# Seeeduino_LoRaWan.net
KiCad netlist of a schematic drawn in EAGLE
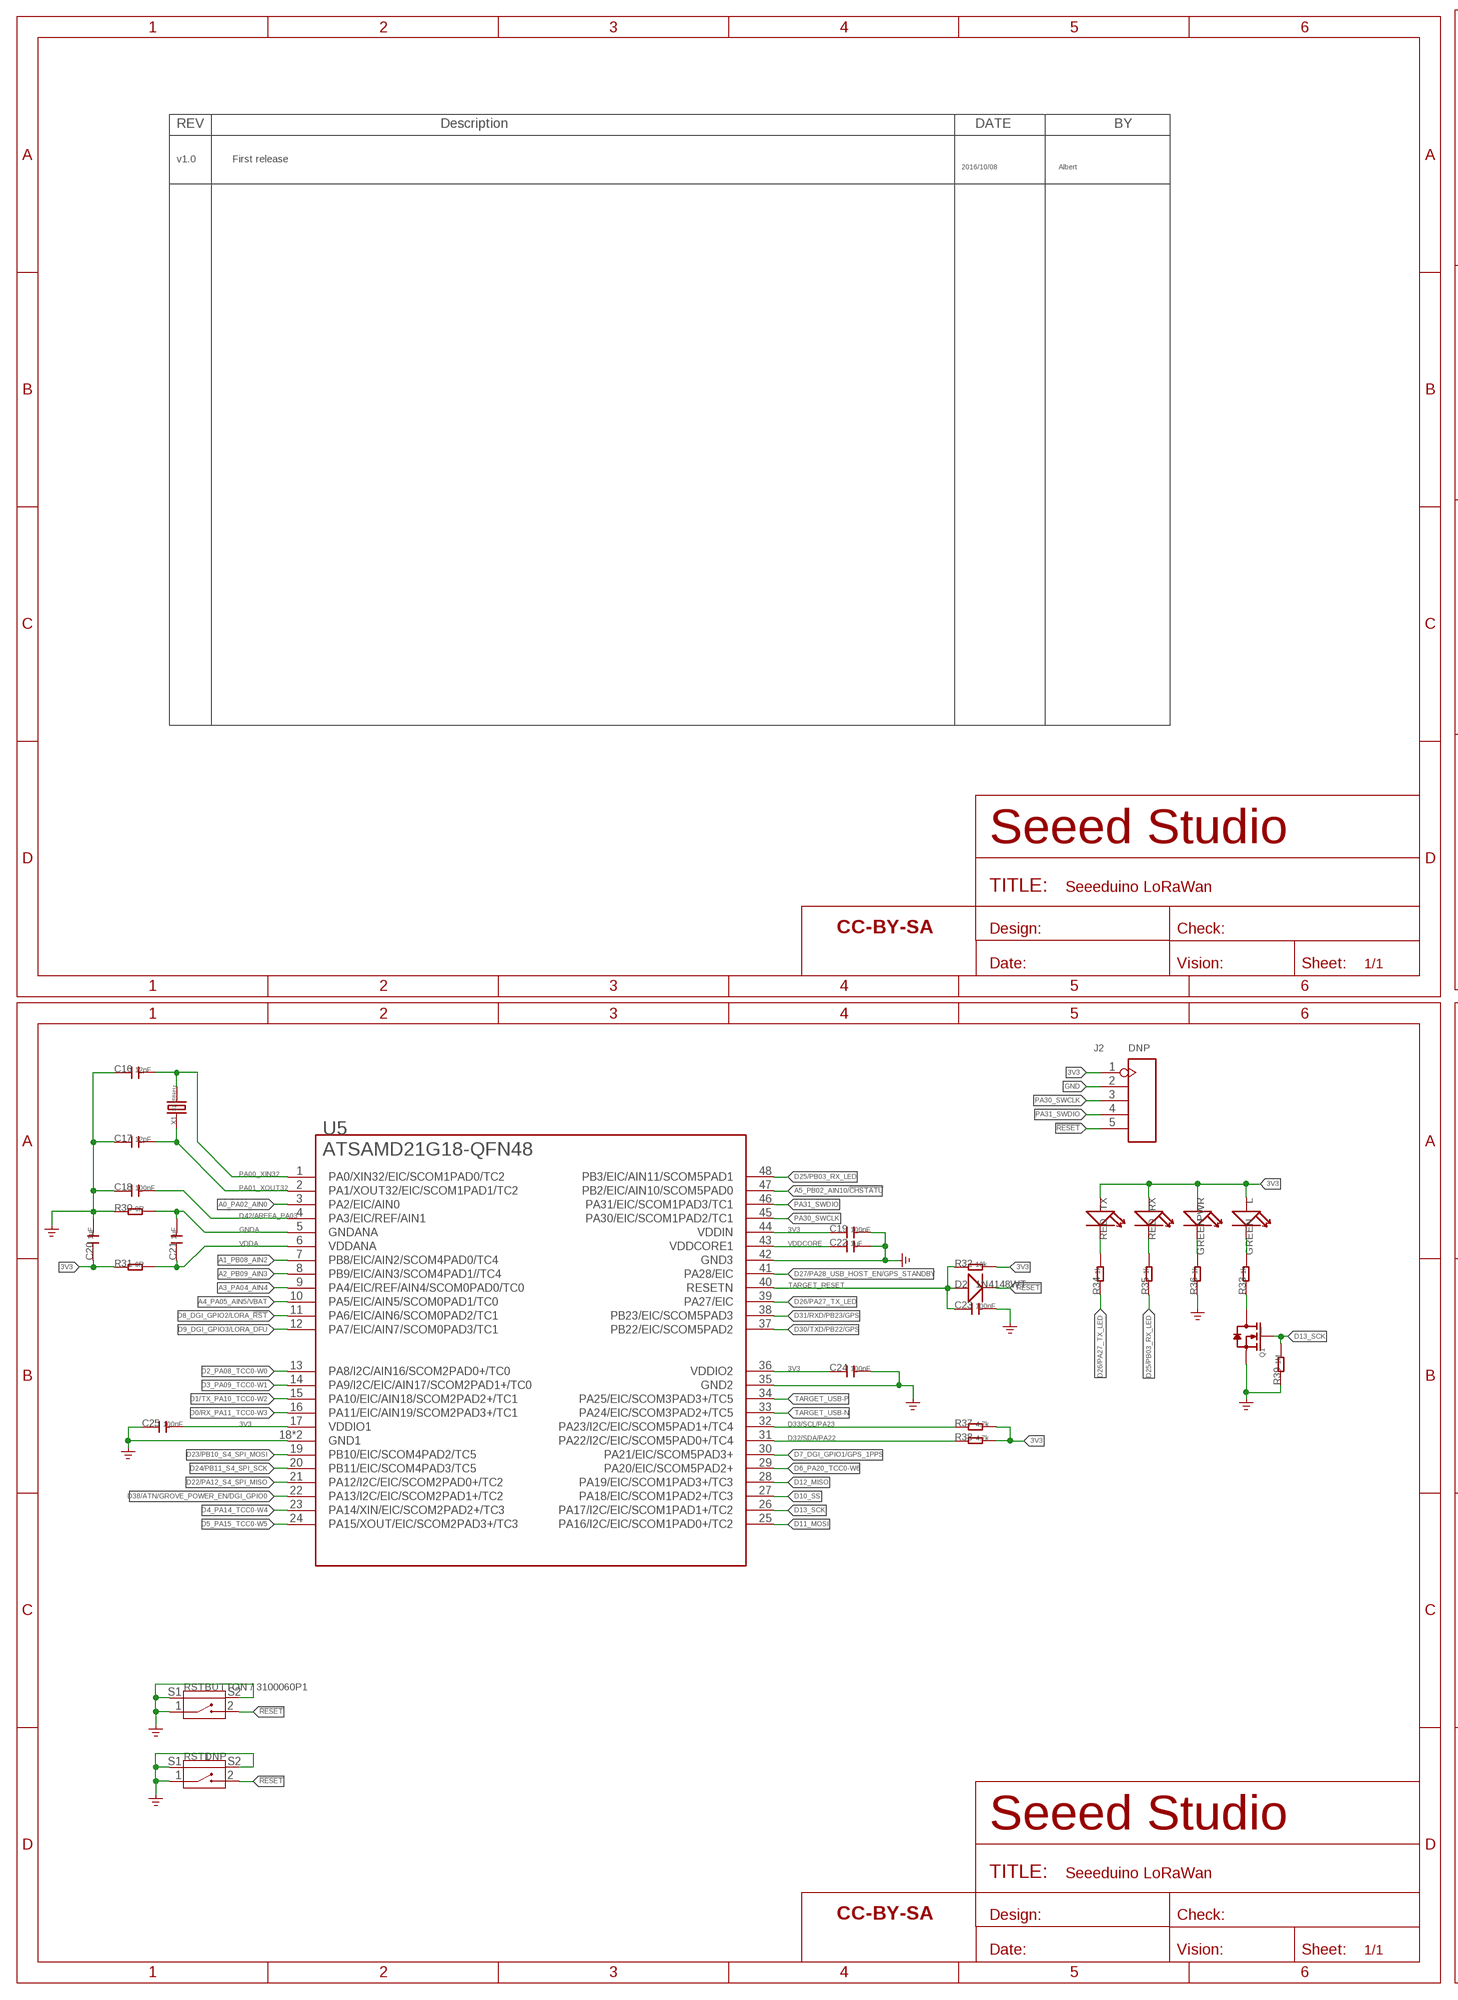
[diagram p0: schematic, sheet 1, part 1 of 2]
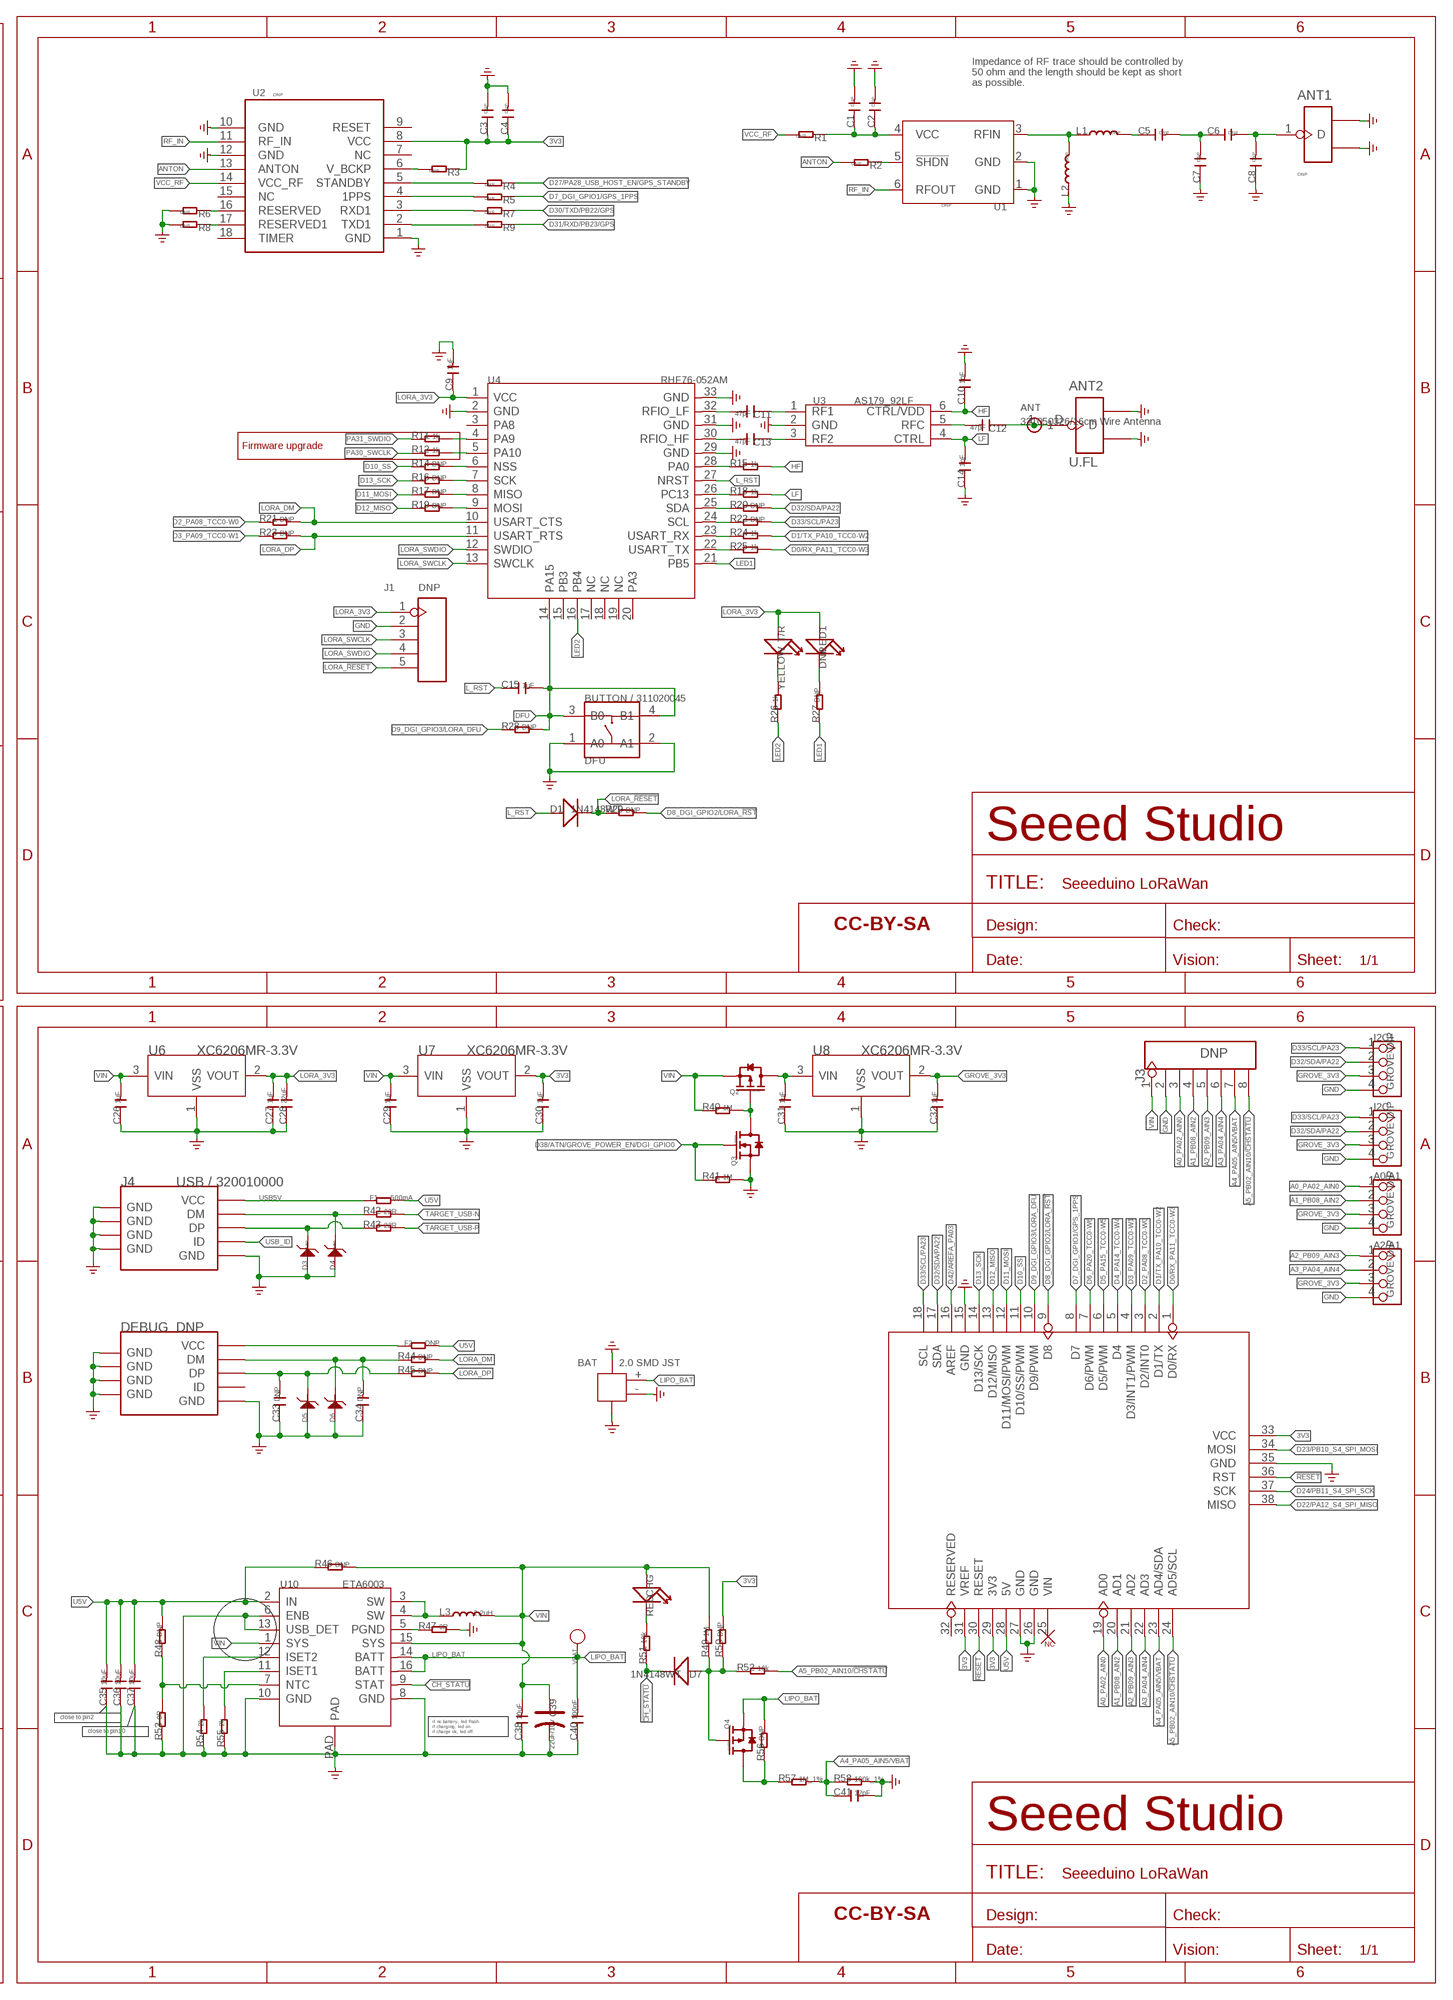
[diagram p1: schematic, sheet 1, part 2 of 2]

(export (version "E")
  (design (tool "Eeschema 10.0.6"))
  (components
    (comp (ref "A0/A1")
      (value "GROVE-DIP")
      (footprint "eagle-import:4P-2.0")
      (libsource (lib "eagle-import") (part "TWIG-4P-2.0-2.0"))
    )
    (comp (ref "A2/A1")
      (value "GROVE-DIP")
      (footprint "eagle-import:4P-2.0")
      (libsource (lib "eagle-import") (part "TWIG-4P-2.0-2.0"))
    )
    (comp (ref "ANT")
      (value "321050326/16cm Wire Antenna")
      (footprint "eagle-import:1P-65_35MIL")
      (libsource (lib "eagle-import") (part "HEADER-1P-35"))
    )
    (comp (ref "ANT1")
      (value "DNP")
      (footprint "eagle-import:ANT3-SMD-5.2X3.7X0.7MM")
      (fields (field (name "MPN") "ACD-5036-A3-CC-S"))
      (libsource (lib "eagle-import") (part "ANTENNA-ACD5036"))
    )
    (comp (ref "ANT2")
      (value "U.FL")
      (footprint "eagle-import:U-FL3P-SMD-2.6X2.6X1.0MM")
      (libsource (lib "eagle-import") (part "ANTENNA-U-FL"))
    )
    (comp (ref "BAT")
      (value "2.0 SMD JST")
      (footprint "eagle-import:HW2-SMD-2.0-90D")
      (libsource (lib "eagle-import") (part "JST-2P-SMD'2.0'"))
    )
    (comp (ref "C1")
      (value "DNP")
      (footprint "eagle-import:C0402")
      (libsource (lib "eagle-import") (part "C-0402"))
    )
    (comp (ref "C2")
      (value "DNP")
      (footprint "eagle-import:C0402")
      (libsource (lib "eagle-import") (part "C-0402"))
    )
    (comp (ref "C3")
      (value "DNP")
      (footprint "eagle-import:C0402")
      (libsource (lib "eagle-import") (part "C-0402"))
    )
    (comp (ref "C4")
      (value "DNP")
      (footprint "eagle-import:C0603")
      (libsource (lib "eagle-import") (part "C-0603"))
    )
    (comp (ref "C5")
      (value "DNP")
      (footprint "eagle-import:C0402")
      (libsource (lib "eagle-import") (part "C-0402"))
    )
    (comp (ref "C6")
      (value "DNP")
      (footprint "eagle-import:C0402")
      (libsource (lib "eagle-import") (part "C-0402"))
    )
    (comp (ref "C7")
      (value "DNP")
      (footprint "eagle-import:C0402")
      (libsource (lib "eagle-import") (part "C-0402"))
    )
    (comp (ref "C8")
      (value "DNP")
      (footprint "eagle-import:C0402")
      (libsource (lib "eagle-import") (part "C-0402"))
    )
    (comp (ref "C9")
      (value "1uF")
      (footprint "eagle-import:C0402")
      (libsource (lib "eagle-import") (part "C-0402"))
    )
    (comp (ref "C10")
      (value "1nF")
      (footprint "eagle-import:C0402")
      (libsource (lib "eagle-import") (part "C-0402"))
    )
    (comp (ref "C11")
      (value "47pF")
      (footprint "eagle-import:C0402")
      (libsource (lib "eagle-import") (part "C-0402"))
    )
    (comp (ref "C12")
      (value "47pF")
      (footprint "eagle-import:C0402")
      (libsource (lib "eagle-import") (part "C-0402"))
    )
    (comp (ref "C13")
      (value "47pF")
      (footprint "eagle-import:C0402")
      (libsource (lib "eagle-import") (part "C-0402"))
    )
    (comp (ref "C14")
      (value "1nF")
      (footprint "eagle-import:C0402")
      (libsource (lib "eagle-import") (part "C-0402"))
    )
    (comp (ref "C15")
      (value "1uF")
      (footprint "eagle-import:C0402")
      (libsource (lib "eagle-import") (part "C-0402"))
    )
    (comp (ref "C16")
      (value "12pF")
      (footprint "eagle-import:C0402")
      (libsource (lib "eagle-import") (part "C-0402"))
    )
    (comp (ref "C17")
      (value "12pF")
      (footprint "eagle-import:C0402")
      (libsource (lib "eagle-import") (part "C-0402"))
    )
    (comp (ref "C18")
      (value "100nF")
      (footprint "eagle-import:C0402")
      (libsource (lib "eagle-import") (part "C-0402"))
    )
    (comp (ref "C19")
      (value "100nF")
      (footprint "eagle-import:C0402")
      (libsource (lib "eagle-import") (part "C-0402"))
    )
    (comp (ref "C20")
      (value "1uF")
      (footprint "eagle-import:C0402")
      (libsource (lib "eagle-import") (part "C-0402"))
    )
    (comp (ref "C21")
      (value "1uF")
      (footprint "eagle-import:C0402")
      (libsource (lib "eagle-import") (part "C-0402"))
    )
    (comp (ref "C22")
      (value "1uF")
      (footprint "eagle-import:C0402")
      (libsource (lib "eagle-import") (part "C-0402"))
    )
    (comp (ref "C23")
      (value "100nF")
      (footprint "eagle-import:C0402")
      (libsource (lib "eagle-import") (part "C-0402"))
    )
    (comp (ref "C24")
      (value "100nF")
      (footprint "eagle-import:C0402")
      (libsource (lib "eagle-import") (part "C-0402"))
    )
    (comp (ref "C25")
      (value "100nF")
      (footprint "eagle-import:C0402")
      (libsource (lib "eagle-import") (part "C-0402"))
    )
    (comp (ref "C26")
      (value "1uF")
      (footprint "eagle-import:C0402")
      (libsource (lib "eagle-import") (part "C-0402"))
    )
    (comp (ref "C27")
      (value "1uF")
      (footprint "eagle-import:C0402")
      (libsource (lib "eagle-import") (part "C-0402"))
    )
    (comp (ref "C28")
      (value "22uF")
      (footprint "eagle-import:C0603")
      (libsource (lib "eagle-import") (part "C-0603"))
    )
    (comp (ref "C29")
      (value "1uF")
      (footprint "eagle-import:C0402")
      (libsource (lib "eagle-import") (part "C-0402"))
    )
    (comp (ref "C30")
      (value "1uF")
      (footprint "eagle-import:C0402")
      (libsource (lib "eagle-import") (part "C-0402"))
    )
    (comp (ref "C31")
      (value "1uF")
      (footprint "eagle-import:C0402")
      (libsource (lib "eagle-import") (part "C-0402"))
    )
    (comp (ref "C32")
      (value "1uF")
      (footprint "eagle-import:C0402")
      (libsource (lib "eagle-import") (part "C-0402"))
    )
    (comp (ref "C33")
      (value "DNP")
      (footprint "eagle-import:C0402")
      (libsource (lib "eagle-import") (part "C-0402"))
    )
    (comp (ref "C34")
      (value "DNP")
      (footprint "eagle-import:C0402")
      (libsource (lib "eagle-import") (part "C-0402"))
    )
    (comp (ref "C35")
      (value "10uF")
      (footprint "eagle-import:C0603")
      (libsource (lib "eagle-import") (part "C-0603"))
    )
    (comp (ref "C36")
      (value "10uF")
      (footprint "eagle-import:C0603")
      (libsource (lib "eagle-import") (part "C-0603"))
    )
    (comp (ref "C37")
      (value "10uF")
      (footprint "eagle-import:C0603")
      (libsource (lib "eagle-import") (part "C-0603"))
    )
    (comp (ref "C38")
      (value "10uF")
      (footprint "eagle-import:C0603")
      (libsource (lib "eagle-import") (part "C-0603"))
    )
    (comp (ref "C39")
      (value "22uF/10v")
      (footprint "eagle-import:AVX-A")
      (libsource (lib "eagle-import") (part "CAP-AVX-A"))
    )
    (comp (ref "C40")
      (value "100nF")
      (footprint "eagle-import:C0402")
      (libsource (lib "eagle-import") (part "C-0402"))
    )
    (comp (ref "C41")
      (value "12pF")
      (footprint "eagle-import:C0402")
      (libsource (lib "eagle-import") (part "C-0402"))
    )
    (comp (ref "CHG")
      (value "RED")
      (footprint "eagle-import:LED-0603")
      (libsource (lib "eagle-import") (part "LED'0603'"))
    )
    (comp (ref "D1")
      (value "1N4148WT")
      (footprint "eagle-import:SOD523")
      (libsource (lib "eagle-import") (part "D'0603'"))
    )
    (comp (ref "D2")
      (value "1N4148WT")
      (footprint "eagle-import:SOD523")
      (libsource (lib "eagle-import") (part "D'0603'"))
    )
    (comp (ref "D3")
      (value "DF2S6.8FS")
      (footprint "eagle-import:SOD-923")
      (libsource (lib "eagle-import") (part "D-ESD-2P'DF2S6.8FS'"))
    )
    (comp (ref "D4")
      (value "DF2S6.8FS")
      (footprint "eagle-import:SOD-923")
      (libsource (lib "eagle-import") (part "D-ESD-2P'DF2S6.8FS'"))
    )
    (comp (ref "D5")
      (value "DNP")
      (footprint "eagle-import:SOD-923")
      (libsource (lib "eagle-import") (part "D-ESD-2P'DF2S6.8FS'"))
    )
    (comp (ref "D6")
      (value "DNP")
      (footprint "eagle-import:SOD-923")
      (libsource (lib "eagle-import") (part "D-ESD-2P'DF2S6.8FS'"))
    )
    (comp (ref "D7")
      (value "1N4148WT")
      (footprint "eagle-import:SOD523")
      (libsource (lib "eagle-import") (part "D'0603'"))
    )
    (comp (ref "DEBUG")
      (value "DNP")
      (footprint "eagle-import:MICRO-USB")
      (libsource (lib "eagle-import") (part "USB-MINIUSB-5P-MICRO"))
    )
    (comp (ref "DFU")
      (value "BUTTON / 311020045")
      (footprint "eagle-import:SW4P-SMD-4.5X3.2X2.5MM")
      (libsource (lib "eagle-import") (part "BUTTON-4P-4.5X3.2"))
    )
    (comp (ref "F1")
      (value "500mA")
      (footprint "eagle-import:R0805")
      (libsource (lib "eagle-import") (part "Discrete-smallsmall_R-0805"))
    )
    (comp (ref "F2")
      (value "DNP")
      (footprint "eagle-import:R0805")
      (libsource (lib "eagle-import") (part "Discrete-smallsmall_R-0805"))
    )
    (comp (ref "FR")
      (value "PAGE1")
      (footprint "eagle-import:SEEEDSTUDIO-PCB-FRAME")
      (libsource (lib "eagle-import") (part "SEEEDSTUDIO-OPEN-SCH-FRAME"))
    )
    (comp (ref "FR1")
      (value "PAGE1")
      (footprint "eagle-import:SEEEDSTUDIO-PCB-FRAME")
      (libsource (lib "eagle-import") (part "SEEEDSTUDIO-OPEN-SCH-FRAME"))
    )
    (comp (ref "I2C")
      (value "GROVE-DIP")
      (footprint "eagle-import:4P-2.0")
      (libsource (lib "eagle-import") (part "TWIG-4P-2.0-2.0"))
    )
    (comp (ref "I2C1")
      (value "GROVE-DIP")
      (footprint "eagle-import:4P-2.0")
      (libsource (lib "eagle-import") (part "TWIG-4P-2.0-2.0"))
    )
    (comp (ref "J1")
      (value "DNP")
      (footprint "eagle-import:H5-SMD-2.0-TEST")
      (libsource (lib "eagle-import") (part "HEADER-5P'TEST'"))
    )
    (comp (ref "J2")
      (value "DNP")
      (footprint "eagle-import:H5-SMD-2.0-TEST")
      (libsource (lib "eagle-import") (part "HEADER-5P'TEST'"))
    )
    (comp (ref "J3")
      (value "DNP")
      (footprint "eagle-import:8P-2.54-65_35MIL")
      (libsource (lib "eagle-import") (part "HEADER-8P-65/35MIL"))
    )
    (comp (ref "J4")
      (value "USB / 320010000")
      (footprint "eagle-import:MICRO-USB")
      (libsource (lib "eagle-import") (part "USB-MINIUSB-5P-MICRO"))
    )
    (comp (ref "L")
      (value "GREEN")
      (footprint "eagle-import:LED-0603")
      (libsource (lib "eagle-import") (part "LED'0603'"))
    )
    (comp (ref "L1")
      (value "DNP")
      (footprint "eagle-import:L0402")
      (libsource (lib "eagle-import") (part "L'0402'"))
    )
    (comp (ref "L2")
      (value "DNP")
      (footprint "eagle-import:L0402")
      (libsource (lib "eagle-import") (part "L'0402'"))
    )
    (comp (ref "L3")
      (value "2.2uH")
      (footprint "eagle-import:L0805")
      (libsource (lib "eagle-import") (part "L'0805'"))
    )
    (comp (ref "LED1")
      (value "DNP")
      (footprint "eagle-import:LED-0603")
      (libsource (lib "eagle-import") (part "LED'0603'"))
    )
    (comp (ref "PWR")
      (value "GREEN")
      (footprint "eagle-import:LED-0603")
      (libsource (lib "eagle-import") (part "LED'0603'"))
    )
    (comp (ref "Q1")
      (value "CJ2102")
      (footprint "eagle-import:SOT-323")
      (libsource (lib "eagle-import") (part "MOSFET-N'SI1304BDL'"))
    )
    (comp (ref "Q2")
      (value "CJ2101")
      (footprint "eagle-import:SOT323")
      (libsource (lib "eagle-import") (part "MOSFET-P-SOT323"))
    )
    (comp (ref "Q3")
      (value "CJ2102")
      (footprint "eagle-import:SOT-323")
      (libsource (lib "eagle-import") (part "MOSFET-N'SI1304BDL'"))
    )
    (comp (ref "Q4")
      (value "CJ2101")
      (footprint "eagle-import:SOT323")
      (libsource (lib "eagle-import") (part "MOSFET-P-SOT323"))
    )
    (comp (ref "R1")
      (value "DNP")
      (footprint "eagle-import:R0402")
      (libsource (lib "eagle-import") (part "R-0402"))
    )
    (comp (ref "R2")
      (value "DNP")
      (footprint "eagle-import:R0402")
      (libsource (lib "eagle-import") (part "R-0402"))
    )
    (comp (ref "R3")
      (value "DNP")
      (footprint "eagle-import:R0402")
      (libsource (lib "eagle-import") (part "R-0402"))
    )
    (comp (ref "R4")
      (value "DNP")
      (footprint "eagle-import:R0402")
      (libsource (lib "eagle-import") (part "R-0402"))
    )
    (comp (ref "R5")
      (value "DNP")
      (footprint "eagle-import:R0402")
      (libsource (lib "eagle-import") (part "R-0402"))
    )
    (comp (ref "R6")
      (value "DNP")
      (footprint "eagle-import:R0402")
      (libsource (lib "eagle-import") (part "R-0402"))
    )
    (comp (ref "R7")
      (value "DNP")
      (footprint "eagle-import:R0402")
      (libsource (lib "eagle-import") (part "R-0402"))
    )
    (comp (ref "R8")
      (value "DNP")
      (footprint "eagle-import:R0402")
      (libsource (lib "eagle-import") (part "R-0402"))
    )
    (comp (ref "R9")
      (value "DNP")
      (footprint "eagle-import:R0402")
      (libsource (lib "eagle-import") (part "R-0402"))
    )
    (comp (ref "R11")
      (value "1k")
      (footprint "eagle-import:R0402")
      (libsource (lib "eagle-import") (part "R-0402"))
    )
    (comp (ref "R12")
      (value "1k")
      (footprint "eagle-import:R0402")
      (libsource (lib "eagle-import") (part "R-0402"))
    )
    (comp (ref "R14")
      (value "DNP")
      (footprint "eagle-import:R0402")
      (libsource (lib "eagle-import") (part "R-0402"))
    )
    (comp (ref "R15")
      (value "1k")
      (footprint "eagle-import:R0402")
      (libsource (lib "eagle-import") (part "R-0402"))
    )
    (comp (ref "R16")
      (value "DNP")
      (footprint "eagle-import:R0402")
      (libsource (lib "eagle-import") (part "R-0402"))
    )
    (comp (ref "R17")
      (value "DNP")
      (footprint "eagle-import:R0402")
      (libsource (lib "eagle-import") (part "R-0402"))
    )
    (comp (ref "R18")
      (value "1k")
      (footprint "eagle-import:R0402")
      (libsource (lib "eagle-import") (part "R-0402"))
    )
    (comp (ref "R19")
      (value "DNP")
      (footprint "eagle-import:R0402")
      (libsource (lib "eagle-import") (part "R-0402"))
    )
    (comp (ref "R20")
      (value "DNP")
      (footprint "eagle-import:R0402")
      (libsource (lib "eagle-import") (part "R-0402"))
    )
    (comp (ref "R21")
      (value "DNP")
      (footprint "eagle-import:R0402")
      (libsource (lib "eagle-import") (part "R-0402"))
    )
    (comp (ref "R22")
      (value "DNP")
      (footprint "eagle-import:R0402")
      (libsource (lib "eagle-import") (part "R-0402"))
    )
    (comp (ref "R23")
      (value "DNP")
      (footprint "eagle-import:R0402")
      (libsource (lib "eagle-import") (part "R-0402"))
    )
    (comp (ref "R24")
      (value "1k")
      (footprint "eagle-import:R0402")
      (libsource (lib "eagle-import") (part "R-0402"))
    )
    (comp (ref "R25")
      (value "1k")
      (footprint "eagle-import:R0402")
      (libsource (lib "eagle-import") (part "R-0402"))
    )
    (comp (ref "R26")
      (value "1k")
      (footprint "eagle-import:R0402")
      (libsource (lib "eagle-import") (part "R-0402"))
    )
    (comp (ref "R27")
      (value "DNP")
      (footprint "eagle-import:R0402")
      (libsource (lib "eagle-import") (part "R-0402"))
    )
    (comp (ref "R28")
      (value "DNP")
      (footprint "eagle-import:R0402")
      (libsource (lib "eagle-import") (part "R-0402"))
    )
    (comp (ref "R29")
      (value "DNP")
      (footprint "eagle-import:R0402")
      (libsource (lib "eagle-import") (part "R-0402"))
    )
    (comp (ref "R30")
      (value "0R")
      (footprint "eagle-import:R0402")
      (libsource (lib "eagle-import") (part "R-0402"))
    )
    (comp (ref "R31")
      (value "0R")
      (footprint "eagle-import:R0402")
      (libsource (lib "eagle-import") (part "R-0402"))
    )
    (comp (ref "R32")
      (value "10k")
      (footprint "eagle-import:R0402")
      (libsource (lib "eagle-import") (part "R-0402"))
    )
    (comp (ref "R33")
      (value "1k")
      (footprint "eagle-import:R0402")
      (libsource (lib "eagle-import") (part "R-0402"))
    )
    (comp (ref "R34")
      (value "1k")
      (footprint "eagle-import:R0402")
      (libsource (lib "eagle-import") (part "R-0402"))
    )
    (comp (ref "R35")
      (value "1k")
      (footprint "eagle-import:R0402")
      (libsource (lib "eagle-import") (part "R-0402"))
    )
    (comp (ref "R36")
      (value "1k")
      (footprint "eagle-import:R0402")
      (libsource (lib "eagle-import") (part "R-0402"))
    )
    (comp (ref "R37")
      (value "4.7k")
      (footprint "eagle-import:R0402")
      (libsource (lib "eagle-import") (part "R-0402"))
    )
    (comp (ref "R38")
      (value "4.7k")
      (footprint "eagle-import:R0402")
      (libsource (lib "eagle-import") (part "R-0402"))
    )
    (comp (ref "R39")
      (value "1M")
      (footprint "eagle-import:R0402")
      (libsource (lib "eagle-import") (part "R-0402"))
    )
    (comp (ref "R40")
      (value "1M")
      (footprint "eagle-import:R0402")
      (libsource (lib "eagle-import") (part "R-0402"))
    )
    (comp (ref "R41")
      (value "1M")
      (footprint "eagle-import:R0402")
      (libsource (lib "eagle-import") (part "R-0402"))
    )
    (comp (ref "R42")
      (value "22R")
      (footprint "eagle-import:R0402")
      (libsource (lib "eagle-import") (part "R-0402"))
    )
    (comp (ref "R43")
      (value "22R")
      (footprint "eagle-import:R0402")
      (libsource (lib "eagle-import") (part "R-0402"))
    )
    (comp (ref "R44")
      (value "DNP")
      (footprint "eagle-import:R0402")
      (libsource (lib "eagle-import") (part "R-0402"))
    )
    (comp (ref "R45")
      (value "DNP")
      (footprint "eagle-import:R0402")
      (libsource (lib "eagle-import") (part "R-0402"))
    )
    (comp (ref "R46")
      (value "DNP")
      (footprint "eagle-import:R0402")
      (libsource (lib "eagle-import") (part "R-0402"))
    )
    (comp (ref "R47")
      (value "0R")
      (footprint "eagle-import:R0402")
      (libsource (lib "eagle-import") (part "R-0402"))
    )
    (comp (ref "R48")
      (value "DNP")
      (footprint "eagle-import:R0402")
      (libsource (lib "eagle-import") (part "R-0402"))
    )
    (comp (ref "R49")
      (value "1M")
      (footprint "eagle-import:R0402")
      (libsource (lib "eagle-import") (part "R-0402"))
    )
    (comp (ref "R50")
      (value "DNP")
      (footprint "eagle-import:R0402")
      (libsource (lib "eagle-import") (part "R-0402"))
    )
    (comp (ref "R51")
      (value "10k")
      (footprint "eagle-import:R0402")
      (libsource (lib "eagle-import") (part "R-0402"))
    )
    (comp (ref "R52")
      (value "10k")
      (footprint "eagle-import:R0402")
      (libsource (lib "eagle-import") (part "R-0402"))
    )
    (comp (ref "R53")
      (value "0R")
      (footprint "eagle-import:R0402")
      (libsource (lib "eagle-import") (part "R-0402"))
    )
    (comp (ref "R54")
      (value "2k")
      (footprint "eagle-import:R0402")
      (libsource (lib "eagle-import") (part "R-0402"))
    )
    (comp (ref "R55")
      (value "2k")
      (footprint "eagle-import:R0402")
      (libsource (lib "eagle-import") (part "R-0402"))
    )
    (comp (ref "R56")
      (value "DNP")
      (footprint "eagle-import:R0402")
      (libsource (lib "eagle-import") (part "R-0402"))
    )
    (comp (ref "R57")
      (value "1M_1%")
      (footprint "eagle-import:R0402")
      (libsource (lib "eagle-import") (part "R-0402"))
    )
    (comp (ref "R58")
      (value "100k_1%")
      (footprint "eagle-import:R0402")
      (libsource (lib "eagle-import") (part "R-0402"))
    )
    (comp (ref "RST")
      (value "BUTTON / 3100060P1")
      (footprint "eagle-import:4P-SMD-7.0X3.5X3.5H-90D")
      (libsource (lib "eagle-import") (part "BUTTON-2P-REINFORCE-3100060P1"))
    )
    (comp (ref "RST1")
      (value "DNP")
      (footprint "eagle-import:4P-SMD-7.0X3.5X3.5H-90D")
      (libsource (lib "eagle-import") (part "BUTTON-2P-REINFORCE-3100060P1"))
    )
    (comp (ref "RX")
      (value "RED")
      (footprint "eagle-import:LED-0603")
      (libsource (lib "eagle-import") (part "LED'0603'"))
    )
    (comp (ref "T/R")
      (value "YELLOW")
      (footprint "eagle-import:LED-0603")
      (libsource (lib "eagle-import") (part "LED'0603'"))
    )
    (comp (ref "TX")
      (value "RED")
      (footprint "eagle-import:LED-0603")
      (libsource (lib "eagle-import") (part "LED'0603'"))
    )
    (comp (ref "U$2")
      (value "SEEEDSTUDIO-OPEN-SCH-FRAME")
      (footprint "eagle-import:SEEEDSTUDIO-PCB-FRAME")
      (libsource (lib "eagle-import") (part "SEEEDSTUDIO-OPEN-SCH-FRAME"))
    )
    (comp (ref "U$3")
      (value "SEEEDSTUDIO-OPEN-SCH-FRAME")
      (footprint "eagle-import:SEEEDSTUDIO-PCB-FRAME")
      (libsource (lib "eagle-import") (part "SEEEDSTUDIO-OPEN-SCH-FRAME"))
    )
    (comp (ref "U1")
      (value "DNP")
      (footprint "eagle-import:DFN6-0.5-1.5X1.2X0.72MM")
      (fields (field (name "MPN") "MAX2659"))
      (libsource (lib "eagle-import") (part "AMPLIFIER-MAX2659"))
    )
    (comp (ref "U2")
      (value "DNP")
      (footprint "eagle-import:LGA18-1.1-9.7X10.1X2.5MM")
      (fields (field (name "MPN") "L70"))
      (libsource (lib "eagle-import") (part "MOUDLE-GPS-L70-HARDWARE"))
    )
    (comp (ref "U3")
      (value "AS179_92LF")
      (footprint "eagle-import:SC-70")
      (libsource (lib "eagle-import") (part "PE4259"))
    )
    (comp (ref "U4")
      (value "RHF76-052AM")
      (footprint "eagle-import:MODULE33P-SMD-2.0-28X23X2.9MM")
      (libsource (lib "eagle-import") (part "MODULE-LORAWAN-RHF76-052"))
    )
    (comp (ref "U5")
      (value "ATSAMD21G18-QFN48")
      (footprint "eagle-import:QFN48-7X7")
      (libsource (lib "eagle-import") (part "ATSAMD21G18-QFN48"))
    )
    (comp (ref "U6")
      (value "XC6206MR-3.3V")
      (footprint "eagle-import:SOT23")
      (libsource (lib "eagle-import") (part "XC6206MR"))
    )
    (comp (ref "U7")
      (value "XC6206MR-3.3V")
      (footprint "eagle-import:SOT23")
      (libsource (lib "eagle-import") (part "XC6206MR"))
    )
    (comp (ref "U8")
      (value "XC6206MR-3.3V")
      (footprint "eagle-import:SOT23")
      (libsource (lib "eagle-import") (part "XC6206MR"))
    )
    (comp (ref "U9")
      (value "ARDUINO-38P")
      (footprint "eagle-import:ARDUINO-38P")
      (libsource (lib "eagle-import") (part "ARDUINO-38P"))
    )
    (comp (ref "U10")
      (value "ETA6003")
      (footprint "eagle-import:QFN16G-0.5-3X3MM")
      (libsource (lib "eagle-import") (part "PMIC-ETA6003"))
    )
    (comp (ref "VBAT")
      (value "DNP")
      (footprint "eagle-import:TP_4545")
      (libsource (lib "eagle-import") (part "PAD-TEST-POINT'4545'"))
    )
    (comp (ref "X1")
      (value "32.768kHz")
      (footprint "eagle-import:X2-SMD-3.2X1.5X0.55MM")
      (libsource (lib "eagle-import") (part "CRYSTAL-2P-3215"))
    )
  )
  (nets
    (net (code "1") (name "/A5_PB02_AIN10{slash}~{CHSTATU}") (class "Default")
      (node (ref "J3") (pin "8") (pinfunction "8_8") (pintype "bidirectional"))
      (node (ref "R52") (pin "2") (pinfunction "2_2") (pintype "passive"))
      (node (ref "U5") (pin "47") (pinfunction "PB2/EIC/AIN10/SCOM5PAD0_47") (pintype "bidirectional"))
      (node (ref "U9") (pin "24") (pinfunction "AD5/SCL_24") (pintype "bidirectional"))
    )
    (net (code "2") (name "/D8_DGI_GPIO2{slash}LORA_~{RST}") (class "Default")
      (node (ref "R29") (pin "2") (pinfunction "2_2") (pintype "passive"))
      (node (ref "U5") (pin "11") (pinfunction "PA6/EIC/AIN6/SCOM0PAD2/TC1_11") (pintype "bidirectional"))
      (node (ref "U9") (pin "9") (pinfunction "D8_9") (pintype "bidirectional"))
    )
    (net (code "3") (name "/GNDA") (class "Default")
      (node (ref "C21") (pin "2") (pinfunction "2_2") (pintype "passive"))
      (node (ref "R30") (pin "2") (pinfunction "2_2") (pintype "passive"))
      (node (ref "U5") (pin "5") (pinfunction "GNDANA_5") (pintype "power_in"))
    )
    (net (code "4") (name "/LORA_~{RESET}") (class "Default")
      (node (ref "D1") (pin "-") (pinfunction "-_-") (pintype "passive"))
      (node (ref "J1") (pin "5") (pinfunction "5_5") (pintype "bidirectional"))
      (node (ref "R29") (pin "1") (pinfunction "1_1") (pintype "passive"))
    )
    (net (code "5") (name "/PA00_XIN32") (class "Default")
      (node (ref "C16") (pin "2") (pinfunction "2_2") (pintype "passive"))
      (node (ref "U5") (pin "1") (pinfunction "PA0/XIN32/EIC/SCOM1PAD0/TC2_1") (pintype "bidirectional"))
      (node (ref "X1") (pin "2") (pinfunction "2_2") (pintype "passive"))
    )
    (net (code "6") (name "/PA01_XOUT32") (class "Default")
      (node (ref "C17") (pin "2") (pinfunction "2_2") (pintype "passive"))
      (node (ref "U5") (pin "2") (pinfunction "PA1/XOUT32/EIC/SCOM1PAD1/TC2_2") (pintype "bidirectional"))
      (node (ref "X1") (pin "1") (pinfunction "1_1") (pintype "passive"))
    )
    (net (code "7") (name "/TARGET_RESET") (class "Default")
      (node (ref "C23") (pin "1") (pinfunction "1_1") (pintype "passive"))
      (node (ref "D2") (pin "+") (pinfunction "+_+") (pintype "passive"))
      (node (ref "R32") (pin "1") (pinfunction "1_1") (pintype "passive"))
      (node (ref "U5") (pin "40") (pinfunction "RESETN_40") (pintype "bidirectional"))
    )
    (net (code "8") (name "/USB5V") (class "Default")
      (node (ref "F1") (pin "1") (pinfunction "1_1") (pintype "passive"))
      (node (ref "J4") (pin "1") (pinfunction "VCC_1") (pintype "bidirectional"))
    )
    (net (code "9") (name "/VDDA") (class "Default")
      (node (ref "C21") (pin "1") (pinfunction "1_1") (pintype "passive"))
      (node (ref "R31") (pin "2") (pinfunction "2_2") (pintype "passive"))
      (node (ref "U5") (pin "6") (pinfunction "VDDANA_6") (pintype "power_in"))
    )
    (net (code "10") (name "/VDDCORE") (class "Default")
      (node (ref "C22") (pin "1") (pinfunction "1_1") (pintype "passive"))
      (node (ref "U5") (pin "43") (pinfunction "VDDCORE1_43") (pintype "input"))
    )
    (net (code "11") (name "/~{CH_STATU}") (class "Default")
      (node (ref "D7") (pin "-") (pinfunction "-_-") (pintype "passive"))
      (node (ref "R51") (pin "1") (pinfunction "1_1") (pintype "passive"))
      (node (ref "U10") (pin "9") (pinfunction "STAT_9") (pintype "bidirectional"))
    )
    (net (code "12") (name "/~{RESET}") (class "Default")
      (node (ref "D2") (pin "-") (pinfunction "-_-") (pintype "passive"))
      (node (ref "J2") (pin "5") (pinfunction "5_5") (pintype "bidirectional"))
      (node (ref "RST") (pin "2") (pinfunction "2_2") (pintype "bidirectional"))
      (node (ref "RST1") (pin "2") (pinfunction "2_2") (pintype "bidirectional"))
      (node (ref "U9") (pin "30") (pinfunction "RESET_30") (pintype "bidirectional"))
      (node (ref "U9") (pin "36") (pinfunction "RST_36") (pintype "bidirectional"))
    )
    (net (code "13") (name "3V3") (class "Default")
      (node (ref "C19") (pin "1") (pinfunction "1_1") (pintype "passive"))
      (node (ref "C20") (pin "1") (pinfunction "1_1") (pintype "passive"))
      (node (ref "C24") (pin "1") (pinfunction "1_1") (pintype "passive"))
      (node (ref "C25") (pin "2") (pinfunction "2_2") (pintype "passive"))
      (node (ref "C3") (pin "1") (pinfunction "1_1") (pintype "passive"))
      (node (ref "C30") (pin "2") (pinfunction "2_2") (pintype "passive"))
      (node (ref "C4") (pin "1") (pinfunction "1_1") (pintype "passive"))
      (node (ref "J2") (pin "1") (pinfunction "1_1") (pintype "bidirectional"))
      (node (ref "L") (pin "+") (pinfunction "+_+") (pintype "passive"))
      (node (ref "PWR") (pin "+") (pinfunction "+_+") (pintype "passive"))
      (node (ref "R3") (pin "1") (pinfunction "1_1") (pintype "passive"))
      (node (ref "R31") (pin "1") (pinfunction "1_1") (pintype "passive"))
      (node (ref "R32") (pin "2") (pinfunction "2_2") (pintype "passive"))
      (node (ref "R37") (pin "2") (pinfunction "2_2") (pintype "passive"))
      (node (ref "R38") (pin "2") (pinfunction "2_2") (pintype "passive"))
      (node (ref "R50") (pin "2") (pinfunction "2_2") (pintype "passive"))
      (node (ref "RX") (pin "+") (pinfunction "+_+") (pintype "passive"))
      (node (ref "TX") (pin "+") (pinfunction "+_+") (pintype "passive"))
      (node (ref "U2") (pin "8") (pinfunction "VCC_8") (pintype "power_in"))
      (node (ref "U5") (pin "17") (pinfunction "VDDIO1_17") (pintype "power_in"))
      (node (ref "U5") (pin "36") (pinfunction "VDDIO2_36") (pintype "power_in"))
      (node (ref "U5") (pin "44") (pinfunction "VDDIN_44") (pintype "power_in"))
      (node (ref "U7") (pin "2") (pinfunction "VOUT_2") (pintype "output"))
      (node (ref "U9") (pin "29") (pinfunction "3V3_29") (pintype "bidirectional"))
      (node (ref "U9") (pin "31") (pinfunction "VREF_31") (pintype "bidirectional"))
      (node (ref "U9") (pin "33") (pinfunction "VCC_33") (pintype "bidirectional"))
    )
    (net (code "14") (name "A0_PA02_AIN0") (class "Default")
      (node (ref "A0/A1") (pin "1") (pinfunction "1_1") (pintype "bidirectional"))
      (node (ref "J3") (pin "3") (pinfunction "3_3") (pintype "bidirectional"))
      (node (ref "U5") (pin "3") (pinfunction "PA2/EIC/AIN0_3") (pintype "bidirectional"))
      (node (ref "U9") (pin "19") (pinfunction "AD0_19") (pintype "bidirectional"))
    )
    (net (code "15") (name "A1_PB08_AIN2") (class "Default")
      (node (ref "A0/A1") (pin "2") (pinfunction "2_2") (pintype "bidirectional"))
      (node (ref "J3") (pin "4") (pinfunction "4_4") (pintype "bidirectional"))
      (node (ref "U5") (pin "7") (pinfunction "PB8/EIC/AIN2/SCOM4PAD0/TC4_7") (pintype "bidirectional"))
      (node (ref "U9") (pin "20") (pinfunction "AD1_20") (pintype "bidirectional"))
    )
    (net (code "16") (name "A2_PB09_AIN3") (class "Default")
      (node (ref "A2/A1") (pin "1") (pinfunction "1_1") (pintype "bidirectional"))
      (node (ref "J3") (pin "5") (pinfunction "5_5") (pintype "bidirectional"))
      (node (ref "U5") (pin "8") (pinfunction "PB9/EIC/AIN3/SCOM4PAD1//TC4_8") (pintype "bidirectional"))
      (node (ref "U9") (pin "21") (pinfunction "AD2_21") (pintype "bidirectional"))
    )
    (net (code "17") (name "A3_PA04_AIN4") (class "Default")
      (node (ref "A2/A1") (pin "2") (pinfunction "2_2") (pintype "bidirectional"))
      (node (ref "J3") (pin "6") (pinfunction "6_6") (pintype "bidirectional"))
      (node (ref "U5") (pin "9") (pinfunction "PA4/EIC/REF/AIN4/SCOM0PAD0/TC0_9") (pintype "bidirectional"))
      (node (ref "U9") (pin "22") (pinfunction "AD3_22") (pintype "bidirectional"))
    )
    (net (code "18") (name "A4_PA05_AIN5{slash}VBAT") (class "Default")
      (node (ref "C41") (pin "1") (pinfunction "1_1") (pintype "passive"))
      (node (ref "J3") (pin "7") (pinfunction "7_7") (pintype "bidirectional"))
      (node (ref "R57") (pin "2") (pinfunction "2_2") (pintype "passive"))
      (node (ref "R58") (pin "1") (pinfunction "1_1") (pintype "passive"))
      (node (ref "U5") (pin "10") (pinfunction "PA5/EIC/AIN5/SCOM0PAD1/TC0_10") (pintype "bidirectional"))
      (node (ref "U9") (pin "23") (pinfunction "AD4/SDA_23") (pintype "bidirectional"))
    )
    (net (code "19") (name "ANTON") (class "Default")
      (node (ref "R2") (pin "2") (pinfunction "2_2") (pintype "passive"))
      (node (ref "U2") (pin "13") (pinfunction "ANTON_13") (pintype "bidirectional"))
    )
    (net (code "20") (name "D0{slash}RX_PA11_TCC0-W3") (class "Default")
      (node (ref "R25") (pin "2") (pinfunction "2_2") (pintype "passive"))
      (node (ref "U5") (pin "16") (pinfunction "PA11/EIC/AIN19/SCOM2PAD3+/TC1_16") (pintype "bidirectional"))
      (node (ref "U9") (pin "1") (pinfunction "D0/RX_1") (pintype "bidirectional"))
    )
    (net (code "21") (name "D1{slash}TX_PA10_TCC0-W2") (class "Default")
      (node (ref "R24") (pin "2") (pinfunction "2_2") (pintype "passive"))
      (node (ref "U5") (pin "15") (pinfunction "PA10/EIC/AIN18/SCOM2PAD2+/TC1_15") (pintype "bidirectional"))
      (node (ref "U9") (pin "2") (pinfunction "D1/TX_2") (pintype "bidirectional"))
    )
    (net (code "22") (name "D2_PA08_TCC0-W0") (class "Default")
      (node (ref "R21") (pin "1") (pinfunction "1_1") (pintype "passive"))
      (node (ref "U5") (pin "13") (pinfunction "PA8/I2C/AIN16/SCOM2PAD0+/TC0_13") (pintype "bidirectional"))
      (node (ref "U9") (pin "3") (pinfunction "D2/INT0_3") (pintype "bidirectional"))
    )
    (net (code "23") (name "D3_PA09_TCC0-W1") (class "Default")
      (node (ref "R23") (pin "1") (pinfunction "1_1") (pintype "passive"))
      (node (ref "U5") (pin "14") (pinfunction "PA9/I2C/EIC/AIN17/SCOM2PAD1+/TC0_14") (pintype "bidirectional"))
      (node (ref "U9") (pin "4") (pinfunction "D3/INT1/PWM_4") (pintype "bidirectional"))
    )
    (net (code "24") (name "D4_PA14_TCC0-W4") (class "Default")
      (node (ref "U5") (pin "23") (pinfunction "PA14/XIN/EIC/SCOM2PAD2+/TC3_23") (pintype "bidirectional"))
      (node (ref "U9") (pin "5") (pinfunction "D4_5") (pintype "bidirectional"))
    )
    (net (code "25") (name "D5_PA15_TCC0-W5") (class "Default")
      (node (ref "U5") (pin "24") (pinfunction "PA15/XOUT/EIC/SCOM2PAD3+/TC3_24") (pintype "bidirectional"))
      (node (ref "U9") (pin "6") (pinfunction "D5/PWM_6") (pintype "bidirectional"))
    )
    (net (code "26") (name "D6_PA20_TCC0-W6") (class "Default")
      (node (ref "U5") (pin "29") (pinfunction "PA20/EIC/SCOM5PAD2+_29") (pintype "bidirectional"))
      (node (ref "U9") (pin "7") (pinfunction "D6/PWM_7") (pintype "bidirectional"))
    )
    (net (code "27") (name "D7_DGI_GPIO1{slash}GPS_1PPS") (class "Default")
      (node (ref "R5") (pin "1") (pinfunction "1_1") (pintype "passive"))
      (node (ref "U5") (pin "30") (pinfunction "PA21/EIC/SCOM5PAD3+_30") (pintype "bidirectional"))
      (node (ref "U9") (pin "8") (pinfunction "D7_8") (pintype "bidirectional"))
    )
    (net (code "28") (name "D9_DGI_GPIO3{slash}LORA_DFU") (class "Default")
      (node (ref "R28") (pin "1") (pinfunction "1_1") (pintype "passive"))
      (node (ref "U5") (pin "12") (pinfunction "PA7/EIC/AIN7/SCOM0PAD3/TC1_12") (pintype "bidirectional"))
      (node (ref "U9") (pin "10") (pinfunction "D9/PWM_10") (pintype "bidirectional"))
    )
    (net (code "29") (name "D10_SS") (class "Default")
      (node (ref "R14") (pin "1") (pinfunction "1_1") (pintype "passive"))
      (node (ref "U5") (pin "27") (pinfunction "PA18/EIC/SCOM1PAD2+/TC3_27") (pintype "bidirectional"))
      (node (ref "U9") (pin "11") (pinfunction "D10/SS/PWM_11") (pintype "bidirectional"))
    )
    (net (code "30") (name "D11_MOSI") (class "Default")
      (node (ref "R17") (pin "1") (pinfunction "1_1") (pintype "passive"))
      (node (ref "U5") (pin "25") (pinfunction "PA16/I2C/EIC/SCOM1PAD0+/TC2_25") (pintype "bidirectional"))
      (node (ref "U9") (pin "12") (pinfunction "D11/MOSI/PWM_12") (pintype "bidirectional"))
    )
    (net (code "31") (name "D12_MISO") (class "Default")
      (node (ref "R19") (pin "1") (pinfunction "1_1") (pintype "passive"))
      (node (ref "U5") (pin "28") (pinfunction "PA19/EIC/SCOM1PAD3+/TC3_28") (pintype "bidirectional"))
      (node (ref "U9") (pin "13") (pinfunction "D12/MISO_13") (pintype "bidirectional"))
    )
    (net (code "32") (name "D13_SCK") (class "Default")
      (node (ref "Q1") (pin "1") (pinfunction "G_1") (pintype "passive"))
      (node (ref "R16") (pin "1") (pinfunction "1_1") (pintype "passive"))
      (node (ref "R39") (pin "2") (pinfunction "2_2") (pintype "passive"))
      (node (ref "U5") (pin "26") (pinfunction "PA17/I2C/EIC/SCOM1PAD1+/TC2_26") (pintype "bidirectional"))
      (node (ref "U9") (pin "14") (pinfunction "D13/SCK_14") (pintype "bidirectional"))
    )
    (net (code "33") (name "D22{slash}PA12_S4_SPI_MISO") (class "Default")
      (node (ref "U5") (pin "21") (pinfunction "PA12/I2C/EIC/SCOM2PAD0+/TC2_21") (pintype "bidirectional"))
      (node (ref "U9") (pin "38") (pinfunction "MISO_38") (pintype "bidirectional"))
    )
    (net (code "34") (name "D23{slash}PB10_S4_SPI_MOSI") (class "Default")
      (node (ref "U5") (pin "19") (pinfunction "PB10/EIC/SCOM4PAD2/TC5_19") (pintype "bidirectional"))
      (node (ref "U9") (pin "34") (pinfunction "MOSI_34") (pintype "bidirectional"))
    )
    (net (code "35") (name "D24{slash}PB11_S4_SPI_SCK") (class "Default")
      (node (ref "U5") (pin "20") (pinfunction "PB11/EIC/SCOM4PAD3/TC5_20") (pintype "bidirectional"))
      (node (ref "U9") (pin "37") (pinfunction "SCK_37") (pintype "bidirectional"))
    )
    (net (code "36") (name "D25{slash}PB03_RX_LED") (class "Default")
      (node (ref "R35") (pin "1") (pinfunction "1_1") (pintype "passive"))
      (node (ref "U5") (pin "48") (pinfunction "PB3/EIC/AIN11/SCOM5PAD1_48") (pintype "bidirectional"))
    )
    (net (code "37") (name "D26{slash}PA27_TX_LED") (class "Default")
      (node (ref "R34") (pin "1") (pinfunction "1_1") (pintype "passive"))
      (node (ref "U5") (pin "39") (pinfunction "PA27/EIC_39") (pintype "bidirectional"))
    )
    (net (code "38") (name "D27{slash}PA28_USB_HOST_EN{slash}GPS_STANDBY") (class "Default")
      (node (ref "R4") (pin "1") (pinfunction "1_1") (pintype "passive"))
      (node (ref "U5") (pin "41") (pinfunction "PA28/EIC_41") (pintype "bidirectional"))
    )
    (net (code "39") (name "D30{slash}TXD{slash}PB22{slash}GPS") (class "Default")
      (node (ref "R7") (pin "1") (pinfunction "1_1") (pintype "passive"))
      (node (ref "U5") (pin "37") (pinfunction "PB22/EIC/SCOM5PAD2_37") (pintype "bidirectional"))
    )
    (net (code "40") (name "D31{slash}RXD{slash}PB23{slash}GPS") (class "Default")
      (node (ref "R9") (pin "1") (pinfunction "1_1") (pintype "passive"))
      (node (ref "U5") (pin "38") (pinfunction "PB23/EIC/SCOM5PAD3_38") (pintype "bidirectional"))
    )
    (net (code "41") (name "D32{slash}SDA{slash}PA22") (class "Default")
      (node (ref "I2C") (pin "2") (pinfunction "2_2") (pintype "bidirectional"))
      (node (ref "I2C1") (pin "2") (pinfunction "2_2") (pintype "bidirectional"))
      (node (ref "R20") (pin "2") (pinfunction "2_2") (pintype "passive"))
      (node (ref "R38") (pin "1") (pinfunction "1_1") (pintype "passive"))
      (node (ref "U5") (pin "31") (pinfunction "PA22/I2C/EIC/SCOM5PAD0+/TC4_31") (pintype "bidirectional"))
      (node (ref "U9") (pin "17") (pinfunction "SDA_17") (pintype "bidirectional"))
    )
    (net (code "42") (name "D33{slash}SCL{slash}PA23") (class "Default")
      (node (ref "I2C") (pin "1") (pinfunction "1_1") (pintype "bidirectional"))
      (node (ref "I2C1") (pin "1") (pinfunction "1_1") (pintype "bidirectional"))
      (node (ref "R22") (pin "2") (pinfunction "2_2") (pintype "passive"))
      (node (ref "R37") (pin "1") (pinfunction "1_1") (pintype "passive"))
      (node (ref "U5") (pin "32") (pinfunction "PA23/I2C/EIC/SCOM5PAD1+/TC4_32") (pintype "bidirectional"))
      (node (ref "U9") (pin "18") (pinfunction "SCL_18") (pintype "bidirectional"))
    )
    (net (code "43") (name "D38{slash}ATN{slash}GROVE_POWER_EN{slash}DGI_GPIO0") (class "Default")
      (node (ref "Q3") (pin "1") (pinfunction "G_1") (pintype "passive"))
      (node (ref "R41") (pin "1") (pinfunction "1_1") (pintype "passive"))
      (node (ref "U5") (pin "22") (pinfunction "PA13/I2C/EIC/SCOM2PAD1+/TC2_22") (pintype "bidirectional"))
    )
    (net (code "44") (name "D42{slash}AREFA_PA03") (class "Default")
      (node (ref "C18") (pin "2") (pinfunction "2_2") (pintype "passive"))
      (node (ref "U5") (pin "4") (pinfunction "PA3/EIC/REF/AIN1_4") (pintype "bidirectional"))
      (node (ref "U9") (pin "16") (pinfunction "AREF_16") (pintype "bidirectional"))
    )
    (net (code "45") (name "DFU") (class "Default")
      (node (ref "C15") (pin "2") (pinfunction "2_2") (pintype "passive"))
      (node (ref "DFU") (pin "3") (pinfunction "B0_3") (pintype "bidirectional"))
      (node (ref "DFU") (pin "4") (pinfunction "B1_4") (pintype "bidirectional"))
      (node (ref "R28") (pin "2") (pinfunction "2_2") (pintype "passive"))
      (node (ref "U4") (pin "14") (pinfunction "PA15_14") (pintype "bidirectional"))
    )
    (net (code "46") (name "GND") (class "Default")
      (node (ref "A0/A1") (pin "4") (pinfunction "4_4") (pintype "bidirectional"))
      (node (ref "A2/A1") (pin "4") (pinfunction "4_4") (pintype "bidirectional"))
      (node (ref "ANT1") (pin "2") (pinfunction "GND1_2") (pintype "bidirectional"))
      (node (ref "ANT1") (pin "3") (pinfunction "GND2_3") (pintype "bidirectional"))
      (node (ref "ANT2") (pin "GND1") (pinfunction "GND1_GND1") (pintype "bidirectional"))
      (node (ref "ANT2") (pin "GND2") (pinfunction "GND2_GND2") (pintype "bidirectional"))
      (node (ref "BAT") (pin "-") (pinfunction "2_-") (pintype "bidirectional"))
      (node (ref "BAT") (pin "3") (pinfunction "3_3") (pintype "bidirectional"))
      (node (ref "BAT") (pin "4") (pinfunction "4_4") (pintype "bidirectional"))
      (node (ref "C1") (pin "2") (pinfunction "2_2") (pintype "passive"))
      (node (ref "C10") (pin "2") (pinfunction "2_2") (pintype "passive"))
      (node (ref "C14") (pin "1") (pinfunction "1_1") (pintype "passive"))
      (node (ref "C16") (pin "1") (pinfunction "1_1") (pintype "passive"))
      (node (ref "C17") (pin "1") (pinfunction "1_1") (pintype "passive"))
      (node (ref "C18") (pin "1") (pinfunction "1_1") (pintype "passive"))
      (node (ref "C19") (pin "2") (pinfunction "2_2") (pintype "passive"))
      (node (ref "C2") (pin "2") (pinfunction "2_2") (pintype "passive"))
      (node (ref "C20") (pin "2") (pinfunction "2_2") (pintype "passive"))
      (node (ref "C22") (pin "2") (pinfunction "2_2") (pintype "passive"))
      (node (ref "C23") (pin "2") (pinfunction "2_2") (pintype "passive"))
      (node (ref "C24") (pin "2") (pinfunction "2_2") (pintype "passive"))
      (node (ref "C25") (pin "1") (pinfunction "1_1") (pintype "passive"))
      (node (ref "C26") (pin "1") (pinfunction "1_1") (pintype "passive"))
      (node (ref "C27") (pin "1") (pinfunction "1_1") (pintype "passive"))
      (node (ref "C28") (pin "1") (pinfunction "1_1") (pintype "passive"))
      (node (ref "C29") (pin "1") (pinfunction "1_1") (pintype "passive"))
      (node (ref "C3") (pin "2") (pinfunction "2_2") (pintype "passive"))
      (node (ref "C30") (pin "1") (pinfunction "1_1") (pintype "passive"))
      (node (ref "C31") (pin "1") (pinfunction "1_1") (pintype "passive"))
      (node (ref "C32") (pin "1") (pinfunction "1_1") (pintype "passive"))
      (node (ref "C33") (pin "1") (pinfunction "1_1") (pintype "passive"))
      (node (ref "C34") (pin "1") (pinfunction "1_1") (pintype "passive"))
      (node (ref "C35") (pin "1") (pinfunction "1_1") (pintype "passive"))
      (node (ref "C36") (pin "1") (pinfunction "1_1") (pintype "passive"))
      (node (ref "C37") (pin "1") (pinfunction "1_1") (pintype "passive"))
      (node (ref "C38") (pin "1") (pinfunction "1_1") (pintype "passive"))
      (node (ref "C39") (pin "-") (pinfunction "-_-") (pintype "passive"))
      (node (ref "C4") (pin "2") (pinfunction "2_2") (pintype "passive"))
      (node (ref "C40") (pin "1") (pinfunction "1_1") (pintype "passive"))
      (node (ref "C41") (pin "2") (pinfunction "2_2") (pintype "passive"))
      (node (ref "C7") (pin "1") (pinfunction "1_1") (pintype "passive"))
      (node (ref "C8") (pin "1") (pinfunction "1_1") (pintype "passive"))
      (node (ref "C9") (pin "2") (pinfunction "2_2") (pintype "passive"))
      (node (ref "D3") (pin "2") (pinfunction "1_2") (pintype "bidirectional"))
      (node (ref "D4") (pin "2") (pinfunction "1_2") (pintype "bidirectional"))
      (node (ref "D5") (pin "2") (pinfunction "1_2") (pintype "bidirectional"))
      (node (ref "D6") (pin "2") (pinfunction "1_2") (pintype "bidirectional"))
      (node (ref "DEBUG") (pin "5") (pinfunction "GND_5") (pintype "bidirectional"))
      (node (ref "DEBUG") (pin "S1") (pinfunction "GND_S1") (pintype "bidirectional"))
      (node (ref "DEBUG") (pin "S2") (pinfunction "GND_S2") (pintype "bidirectional"))
      (node (ref "DEBUG") (pin "S3") (pinfunction "GND_S3") (pintype "bidirectional"))
      (node (ref "DEBUG") (pin "S4") (pinfunction "GND_S4") (pintype "bidirectional"))
      (node (ref "DEBUG") (pin "S5") (pinfunction "GND_S5") (pintype "bidirectional"))
      (node (ref "DEBUG") (pin "S6") (pinfunction "GND_S6") (pintype "bidirectional"))
      (node (ref "DFU") (pin "1") (pinfunction "A0_1") (pintype "bidirectional"))
      (node (ref "DFU") (pin "2") (pinfunction "A1_2") (pintype "bidirectional"))
      (node (ref "I2C") (pin "4") (pinfunction "4_4") (pintype "bidirectional"))
      (node (ref "I2C1") (pin "4") (pinfunction "4_4") (pintype "bidirectional"))
      (node (ref "J1") (pin "2") (pinfunction "2_2") (pintype "bidirectional"))
      (node (ref "J2") (pin "2") (pinfunction "2_2") (pintype "bidirectional"))
      (node (ref "J3") (pin "2") (pinfunction "2_2") (pintype "bidirectional"))
      (node (ref "J4") (pin "5") (pinfunction "GND_5") (pintype "bidirectional"))
      (node (ref "J4") (pin "S1") (pinfunction "GND_S1") (pintype "bidirectional"))
      (node (ref "J4") (pin "S2") (pinfunction "GND_S2") (pintype "bidirectional"))
      (node (ref "J4") (pin "S3") (pinfunction "GND_S3") (pintype "bidirectional"))
      (node (ref "J4") (pin "S4") (pinfunction "GND_S4") (pintype "bidirectional"))
      (node (ref "J4") (pin "S5") (pinfunction "GND_S5") (pintype "bidirectional"))
      (node (ref "J4") (pin "S6") (pinfunction "GND_S6") (pintype "bidirectional"))
      (node (ref "L2") (pin "1") (pinfunction "1_1") (pintype "passive"))
      (node (ref "Q1") (pin "2") (pinfunction "S_2") (pintype "passive"))
      (node (ref "Q3") (pin "2") (pinfunction "S_2") (pintype "passive"))
      (node (ref "R30") (pin "1") (pinfunction "1_1") (pintype "passive"))
      (node (ref "R36") (pin "1") (pinfunction "1_1") (pintype "passive"))
      (node (ref "R39") (pin "1") (pinfunction "1_1") (pintype "passive"))
      (node (ref "R41") (pin "2") (pinfunction "2_2") (pintype "passive"))
      (node (ref "R47") (pin "2") (pinfunction "2_2") (pintype "passive"))
      (node (ref "R53") (pin "1") (pinfunction "1_1") (pintype "passive"))
      (node (ref "R54") (pin "1") (pinfunction "1_1") (pintype "passive"))
      (node (ref "R55") (pin "1") (pinfunction "1_1") (pintype "passive"))
      (node (ref "R58") (pin "2") (pinfunction "2_2") (pintype "passive"))
      (node (ref "R6") (pin "2") (pinfunction "2_2") (pintype "passive"))
      (node (ref "R8") (pin "2") (pinfunction "2_2") (pintype "passive"))
      (node (ref "RST") (pin "1") (pinfunction "1_1") (pintype "bidirectional"))
      (node (ref "RST") (pin "S1") (pinfunction "S1_S1") (pintype "bidirectional"))
      (node (ref "RST") (pin "S2") (pinfunction "S2_S2") (pintype "bidirectional"))
      (node (ref "RST1") (pin "1") (pinfunction "1_1") (pintype "bidirectional"))
      (node (ref "RST1") (pin "S1") (pinfunction "S1_S1") (pintype "bidirectional"))
      (node (ref "RST1") (pin "S2") (pinfunction "S2_S2") (pintype "bidirectional"))
      (node (ref "U1") (pin "1") (pinfunction "GND_1") (pintype "power_in"))
      (node (ref "U1") (pin "2") (pinfunction "GND_2") (pintype "power_in"))
      (node (ref "U10") (pin "10") (pinfunction "GND_10") (pintype "bidirectional"))
      (node (ref "U10") (pin "13") (pinfunction "USB_DET_13") (pintype "bidirectional"))
      (node (ref "U10") (pin "6") (pinfunction "ENB_6") (pintype "bidirectional"))
      (node (ref "U10") (pin "8") (pinfunction "GND_8") (pintype "bidirectional"))
      (node (ref "U10") (pin "PAD") (pinfunction "PAD_PAD") (pintype "bidirectional"))
      (node (ref "U2") (pin "1") (pinfunction "GND_1") (pintype "power_in"))
      (node (ref "U2") (pin "10") (pinfunction "GND_10") (pintype "power_in"))
      (node (ref "U2") (pin "12") (pinfunction "GND_12") (pintype "bidirectional"))
      (node (ref "U3") (pin "2") (pinfunction "GND_2") (pintype "bidirectional"))
      (node (ref "U4") (pin "2") (pinfunction "GND_2") (pintype "bidirectional"))
      (node (ref "U4") (pin "29") (pinfunction "GND_29") (pintype "bidirectional"))
      (node (ref "U4") (pin "31") (pinfunction "GND_31") (pintype "bidirectional"))
      (node (ref "U4") (pin "33") (pinfunction "GND_33") (pintype "bidirectional"))
      (node (ref "U5") (pin "18") (pinfunction "GND1_18") (pintype "power_in"))
      (node (ref "U5") (pin "35") (pinfunction "GND2_35") (pintype "power_in"))
      (node (ref "U5") (pin "42") (pinfunction "GND3_42") (pintype "power_in"))
      (node (ref "U5") (pin "PAD") (pinfunction "GND1_PAD") (pintype "power_in"))
      (node (ref "U6") (pin "1") (pinfunction "VSS_1") (pintype "power_in"))
      (node (ref "U7") (pin "1") (pinfunction "VSS_1") (pintype "power_in"))
      (node (ref "U8") (pin "1") (pinfunction "VSS_1") (pintype "power_in"))
      (node (ref "U9") (pin "15") (pinfunction "GND_15") (pintype "bidirectional"))
      (node (ref "U9") (pin "26") (pinfunction "GND_26") (pintype "bidirectional"))
      (node (ref "U9") (pin "27") (pinfunction "GND_27") (pintype "bidirectional"))
      (node (ref "U9") (pin "35") (pinfunction "GND_35") (pintype "bidirectional"))
    )
    (net (code "47") (name "GROVE_3V3") (class "Default")
      (node (ref "A0/A1") (pin "3") (pinfunction "3_3") (pintype "bidirectional"))
      (node (ref "A2/A1") (pin "3") (pinfunction "3_3") (pintype "bidirectional"))
      (node (ref "C32") (pin "2") (pinfunction "2_2") (pintype "passive"))
      (node (ref "I2C") (pin "3") (pinfunction "3_3") (pintype "bidirectional"))
      (node (ref "I2C1") (pin "3") (pinfunction "3_3") (pintype "bidirectional"))
      (node (ref "U8") (pin "2") (pinfunction "VOUT_2") (pintype "output"))
    )
    (net (code "48") (name "HF") (class "Default")
      (node (ref "C10") (pin "1") (pinfunction "1_1") (pintype "passive"))
      (node (ref "R15") (pin "2") (pinfunction "2_2") (pintype "passive"))
      (node (ref "U3") (pin "6") (pinfunction "~{CTRL}/VDD_6") (pintype "bidirectional"))
    )
    (net (code "49") (name "LED1") (class "Default")
      (node (ref "R27") (pin "1") (pinfunction "1_1") (pintype "passive"))
      (node (ref "U4") (pin "21") (pinfunction "PB5_21") (pintype "bidirectional"))
    )
    (net (code "50") (name "LED2") (class "Default")
      (node (ref "R26") (pin "1") (pinfunction "1_1") (pintype "passive"))
      (node (ref "U4") (pin "16") (pinfunction "PB4_16") (pintype "bidirectional"))
    )
    (net (code "51") (name "LF") (class "Default")
      (node (ref "C14") (pin "2") (pinfunction "2_2") (pintype "passive"))
      (node (ref "R18") (pin "2") (pinfunction "2_2") (pintype "passive"))
      (node (ref "U3") (pin "4") (pinfunction "CTRL_4") (pintype "bidirectional"))
    )
    (net (code "52") (name "LIPO_BAT") (class "Default")
      (node (ref "BAT") (pin "+") (pinfunction "1_+") (pintype "bidirectional"))
      (node (ref "C40") (pin "2") (pinfunction "2_2") (pintype "passive"))
      (node (ref "Q4") (pin "2") (pinfunction "S_2") (pintype "passive"))
      (node (ref "R56") (pin "2") (pinfunction "2_2") (pintype "passive"))
      (node (ref "U10") (pin "14") (pinfunction "BATT_14") (pintype "bidirectional"))
      (node (ref "U10") (pin "16") (pinfunction "BATT_16") (pintype "bidirectional"))
      (node (ref "VBAT") (pin "T") (pinfunction "T_T") (pintype "bidirectional"))
    )
    (net (code "53") (name "LORA_3V3") (class "Default")
      (node (ref "C27") (pin "2") (pinfunction "2_2") (pintype "passive"))
      (node (ref "C28") (pin "2") (pinfunction "2_2") (pintype "passive"))
      (node (ref "C9") (pin "1") (pinfunction "1_1") (pintype "passive"))
      (node (ref "J1") (pin "1") (pinfunction "1_1") (pintype "bidirectional"))
      (node (ref "LED1") (pin "+") (pinfunction "+_+") (pintype "passive"))
      (node (ref "T/R") (pin "+") (pinfunction "+_+") (pintype "passive"))
      (node (ref "U4") (pin "1") (pinfunction "VCC_1") (pintype "bidirectional"))
      (node (ref "U6") (pin "2") (pinfunction "VOUT_2") (pintype "output"))
    )
    (net (code "54") (name "LORA_DM") (class "Default")
      (node (ref "R21") (pin "2") (pinfunction "2_2") (pintype "passive"))
      (node (ref "R44") (pin "2") (pinfunction "2_2") (pintype "passive"))
      (node (ref "U4") (pin "10") (pinfunction "USART_CTS_10") (pintype "bidirectional"))
    )
    (net (code "55") (name "LORA_DP") (class "Default")
      (node (ref "R23") (pin "2") (pinfunction "2_2") (pintype "passive"))
      (node (ref "R45") (pin "2") (pinfunction "2_2") (pintype "passive"))
      (node (ref "U4") (pin "11") (pinfunction "USART_RTS_11") (pintype "bidirectional"))
    )
    (net (code "56") (name "LORA_SWCLK") (class "Default")
      (node (ref "J1") (pin "3") (pinfunction "3_3") (pintype "bidirectional"))
      (node (ref "U4") (pin "13") (pinfunction "SWCLK_13") (pintype "bidirectional"))
    )
    (net (code "57") (name "LORA_SWDIO") (class "Default")
      (node (ref "J1") (pin "4") (pinfunction "4_4") (pintype "bidirectional"))
      (node (ref "U4") (pin "12") (pinfunction "SWDIO_12") (pintype "bidirectional"))
    )
    (net (code "58") (name "L_RST") (class "Default")
      (node (ref "C15") (pin "1") (pinfunction "1_1") (pintype "passive"))
      (node (ref "D1") (pin "+") (pinfunction "+_+") (pintype "passive"))
      (node (ref "U4") (pin "27") (pinfunction "NRST_27") (pintype "bidirectional"))
    )
    (net (code "59") (name "Net-(ANT-Pad1)") (class "Default")
      (node (ref "ANT") (pin "1") (pinfunction "1_1") (pintype "bidirectional"))
      (node (ref "ANT2") (pin "D") (pinfunction "D_D") (pintype "bidirectional"))
      (node (ref "C12") (pin "1") (pinfunction "1_1") (pintype "passive"))
    )
    (net (code "60") (name "Net-(ANT1-D)") (class "Default")
      (node (ref "ANT1") (pin "1") (pinfunction "D_1") (pintype "bidirectional"))
      (node (ref "C6") (pin "2") (pinfunction "2_2") (pintype "passive"))
      (node (ref "C8") (pin "2") (pinfunction "2_2") (pintype "passive"))
    )
    (net (code "61") (name "Net-(C5-Pad1)") (class "Default")
      (node (ref "C5") (pin "1") (pinfunction "1_1") (pintype "passive"))
      (node (ref "L1") (pin "2") (pinfunction "2_2") (pintype "passive"))
    )
    (net (code "62") (name "Net-(C5-Pad2)") (class "Default")
      (node (ref "C5") (pin "2") (pinfunction "2_2") (pintype "passive"))
      (node (ref "C6") (pin "1") (pinfunction "1_1") (pintype "passive"))
      (node (ref "C7") (pin "2") (pinfunction "2_2") (pintype "passive"))
    )
    (net (code "63") (name "Net-(CHG-Pad-)") (class "Default")
      (node (ref "CHG") (pin "-") (pinfunction "-_-") (pintype "passive"))
      (node (ref "R51") (pin "2") (pinfunction "2_2") (pintype "passive"))
    )
    (net (code "64") (name "Net-(D3-2)") (class "Default")
      (node (ref "D3") (pin "1") (pinfunction "2_1") (pintype "bidirectional"))
      (node (ref "J4") (pin "3") (pinfunction "DP_3") (pintype "bidirectional"))
      (node (ref "R43") (pin "1") (pinfunction "1_1") (pintype "passive"))
    )
    (net (code "65") (name "Net-(D4-2)") (class "Default")
      (node (ref "D4") (pin "1") (pinfunction "2_1") (pintype "bidirectional"))
      (node (ref "J4") (pin "2") (pinfunction "DM_2") (pintype "bidirectional"))
      (node (ref "R42") (pin "1") (pinfunction "1_1") (pintype "passive"))
    )
    (net (code "66") (name "Net-(D5-2)") (class "Default")
      (node (ref "C33") (pin "2") (pinfunction "2_2") (pintype "passive"))
      (node (ref "D5") (pin "1") (pinfunction "2_1") (pintype "bidirectional"))
      (node (ref "DEBUG") (pin "3") (pinfunction "DP_3") (pintype "bidirectional"))
      (node (ref "R45") (pin "1") (pinfunction "1_1") (pintype "passive"))
    )
    (net (code "67") (name "Net-(D6-2)") (class "Default")
      (node (ref "C34") (pin "2") (pinfunction "2_2") (pintype "passive"))
      (node (ref "D6") (pin "1") (pinfunction "2_1") (pintype "bidirectional"))
      (node (ref "DEBUG") (pin "2") (pinfunction "DM_2") (pintype "bidirectional"))
      (node (ref "R44") (pin "1") (pinfunction "1_1") (pintype "passive"))
    )
    (net (code "68") (name "Net-(DEBUG-VCC)") (class "Default")
      (node (ref "DEBUG") (pin "1") (pinfunction "VCC_1") (pintype "bidirectional"))
      (node (ref "F2") (pin "1") (pinfunction "1_1") (pintype "passive"))
    )
    (net (code "69") (name "Net-(L-Pad-)") (class "Default")
      (node (ref "L") (pin "-") (pinfunction "-_-") (pintype "passive"))
      (node (ref "R33") (pin "2") (pinfunction "2_2") (pintype "passive"))
    )
    (net (code "70") (name "Net-(L3-Pad1)") (class "Default")
      (node (ref "L3") (pin "1") (pinfunction "1_1") (pintype "passive"))
      (node (ref "U10") (pin "3") (pinfunction "SW_3") (pintype "bidirectional"))
      (node (ref "U10") (pin "4") (pinfunction "SW_4") (pintype "bidirectional"))
    )
    (net (code "71") (name "Net-(LED1-Pad-)") (class "Default")
      (node (ref "LED1") (pin "-") (pinfunction "-_-") (pintype "passive"))
      (node (ref "R27") (pin "2") (pinfunction "2_2") (pintype "passive"))
    )
    (net (code "72") (name "Net-(PWR-Pad-)") (class "Default")
      (node (ref "PWR") (pin "-") (pinfunction "-_-") (pintype "passive"))
      (node (ref "R36") (pin "2") (pinfunction "2_2") (pintype "passive"))
    )
    (net (code "73") (name "Net-(Q1-D)") (class "Default")
      (node (ref "Q1") (pin "3") (pinfunction "D_3") (pintype "passive"))
      (node (ref "R33") (pin "1") (pinfunction "1_1") (pintype "passive"))
    )
    (net (code "74") (name "Net-(Q2-D)") (class "Default")
      (node (ref "C31") (pin "2") (pinfunction "2_2") (pintype "passive"))
      (node (ref "Q2") (pin "3") (pinfunction "D_3") (pintype "passive"))
      (node (ref "U8") (pin "3") (pinfunction "VIN_3") (pintype "input"))
    )
    (net (code "75") (name "Net-(Q2-G)") (class "Default")
      (node (ref "Q2") (pin "1") (pinfunction "G_1") (pintype "passive"))
      (node (ref "Q3") (pin "3") (pinfunction "D_3") (pintype "passive"))
      (node (ref "R40") (pin "2") (pinfunction "2_2") (pintype "passive"))
    )
    (net (code "76") (name "Net-(Q4-D)") (class "Default")
      (node (ref "Q4") (pin "3") (pinfunction "D_3") (pintype "passive"))
      (node (ref "R56") (pin "1") (pinfunction "1_1") (pintype "passive"))
      (node (ref "R57") (pin "1") (pinfunction "1_1") (pintype "passive"))
    )
    (net (code "77") (name "Net-(Q4-G)") (class "Default")
      (node (ref "D7") (pin "+") (pinfunction "+_+") (pintype "passive"))
      (node (ref "Q4") (pin "1") (pinfunction "G_1") (pintype "passive"))
      (node (ref "R49") (pin "1") (pinfunction "1_1") (pintype "passive"))
      (node (ref "R50") (pin "1") (pinfunction "1_1") (pintype "passive"))
      (node (ref "R52") (pin "1") (pinfunction "1_1") (pintype "passive"))
    )
    (net (code "78") (name "Net-(R26-Pad2)") (class "Default")
      (node (ref "R26") (pin "2") (pinfunction "2_2") (pintype "passive"))
      (node (ref "T/R") (pin "-") (pinfunction "-_-") (pintype "passive"))
    )
    (net (code "79") (name "Net-(R34-Pad2)") (class "Default")
      (node (ref "R34") (pin "2") (pinfunction "2_2") (pintype "passive"))
      (node (ref "TX") (pin "-") (pinfunction "-_-") (pintype "passive"))
    )
    (net (code "80") (name "Net-(R35-Pad2)") (class "Default")
      (node (ref "R35") (pin "2") (pinfunction "2_2") (pintype "passive"))
      (node (ref "RX") (pin "-") (pinfunction "-_-") (pintype "passive"))
    )
    (net (code "81") (name "Net-(U1-RFIN)") (class "Default")
      (node (ref "L1") (pin "1") (pinfunction "1_1") (pintype "passive"))
      (node (ref "L2") (pin "2") (pinfunction "2_2") (pintype "passive"))
      (node (ref "U1") (pin "3") (pinfunction "RFIN_3") (pintype "bidirectional"))
    )
    (net (code "82") (name "Net-(U1-VCC)") (class "Default")
      (node (ref "C1") (pin "1") (pinfunction "1_1") (pintype "passive"))
      (node (ref "C2") (pin "1") (pinfunction "1_1") (pintype "passive"))
      (node (ref "R1") (pin "1") (pinfunction "1_1") (pintype "passive"))
      (node (ref "U1") (pin "4") (pinfunction "VCC_4") (pintype "power_in"))
    )
    (net (code "83") (name "Net-(U1-~{SHDN})") (class "Default")
      (node (ref "R2") (pin "1") (pinfunction "1_1") (pintype "passive"))
      (node (ref "U1") (pin "5") (pinfunction "~{SHDN}_5") (pintype "bidirectional"))
    )
    (net (code "84") (name "Net-(U2-1PPS)") (class "Default")
      (node (ref "R5") (pin "2") (pinfunction "2_2") (pintype "passive"))
      (node (ref "U2") (pin "4") (pinfunction "1PPS_4") (pintype "bidirectional"))
    )
    (net (code "85") (name "Net-(U2-RESERVED)") (class "Default")
      (node (ref "R6") (pin "1") (pinfunction "1_1") (pintype "passive"))
      (node (ref "U2") (pin "16") (pinfunction "RESERVED_16") (pintype "bidirectional"))
    )
    (net (code "86") (name "Net-(U2-RESERVED1)") (class "Default")
      (node (ref "R8") (pin "1") (pinfunction "1_1") (pintype "passive"))
      (node (ref "U2") (pin "17") (pinfunction "RESERVED1_17") (pintype "bidirectional"))
    )
    (net (code "87") (name "Net-(U2-RXD1)") (class "Default")
      (node (ref "R7") (pin "2") (pinfunction "2_2") (pintype "passive"))
      (node (ref "U2") (pin "3") (pinfunction "RXD1_3") (pintype "bidirectional"))
    )
    (net (code "88") (name "Net-(U2-STANDBY)") (class "Default")
      (node (ref "R4") (pin "2") (pinfunction "2_2") (pintype "passive"))
      (node (ref "U2") (pin "5") (pinfunction "STANDBY_5") (pintype "bidirectional"))
    )
    (net (code "89") (name "Net-(U2-TXD1)") (class "Default")
      (node (ref "R9") (pin "2") (pinfunction "2_2") (pintype "passive"))
      (node (ref "U2") (pin "2") (pinfunction "TXD1_2") (pintype "bidirectional"))
    )
    (net (code "90") (name "Net-(U2-V_BCKP)") (class "Default")
      (node (ref "R3") (pin "2") (pinfunction "2_2") (pintype "passive"))
      (node (ref "U2") (pin "6") (pinfunction "V_BCKP_6") (pintype "bidirectional"))
    )
    (net (code "91") (name "Net-(U3-RF1)") (class "Default")
      (node (ref "C11") (pin "1") (pinfunction "1_1") (pintype "passive"))
      (node (ref "U3") (pin "1") (pinfunction "RF1_1") (pintype "bidirectional"))
    )
    (net (code "92") (name "Net-(U3-RF2)") (class "Default")
      (node (ref "C13") (pin "1") (pinfunction "1_1") (pintype "passive"))
      (node (ref "U3") (pin "3") (pinfunction "RF2_3") (pintype "bidirectional"))
    )
    (net (code "93") (name "Net-(U3-RFC)") (class "Default")
      (node (ref "C12") (pin "2") (pinfunction "2_2") (pintype "passive"))
      (node (ref "U3") (pin "5") (pinfunction "RFC_5") (pintype "bidirectional"))
    )
    (net (code "94") (name "Net-(U4-MISO)") (class "Default")
      (node (ref "R17") (pin "2") (pinfunction "2_2") (pintype "passive"))
      (node (ref "U4") (pin "8") (pinfunction "MISO_8") (pintype "bidirectional"))
    )
    (net (code "95") (name "Net-(U4-MOSI)") (class "Default")
      (node (ref "R19") (pin "2") (pinfunction "2_2") (pintype "passive"))
      (node (ref "U4") (pin "9") (pinfunction "MOSI_9") (pintype "bidirectional"))
    )
    (net (code "96") (name "Net-(U4-NSS)") (class "Default")
      (node (ref "R14") (pin "2") (pinfunction "2_2") (pintype "passive"))
      (node (ref "U4") (pin "6") (pinfunction "NSS_6") (pintype "bidirectional"))
    )
    (net (code "97") (name "Net-(U4-PA0)") (class "Default")
      (node (ref "R15") (pin "1") (pinfunction "1_1") (pintype "passive"))
      (node (ref "U4") (pin "28") (pinfunction "PA0_28") (pintype "bidirectional"))
    )
    (net (code "98") (name "Net-(U4-PA9)") (class "Default")
      (node (ref "R11") (pin "2") (pinfunction "2_2") (pintype "passive"))
      (node (ref "U4") (pin "4") (pinfunction "PA9_4") (pintype "bidirectional"))
    )
    (net (code "99") (name "Net-(U4-PA10)") (class "Default")
      (node (ref "R12") (pin "2") (pinfunction "2_2") (pintype "passive"))
      (node (ref "U4") (pin "5") (pinfunction "PA10_5") (pintype "bidirectional"))
    )
    (net (code "100") (name "Net-(U4-PC13)") (class "Default")
      (node (ref "R18") (pin "1") (pinfunction "1_1") (pintype "passive"))
      (node (ref "U4") (pin "26") (pinfunction "PC13_26") (pintype "bidirectional"))
    )
    (net (code "101") (name "Net-(U4-RFIO_HF)") (class "Default")
      (node (ref "C13") (pin "2") (pinfunction "2_2") (pintype "passive"))
      (node (ref "U4") (pin "30") (pinfunction "RFIO_HF_30") (pintype "bidirectional"))
    )
    (net (code "102") (name "Net-(U4-RFIO_LF)") (class "Default")
      (node (ref "C11") (pin "2") (pinfunction "2_2") (pintype "passive"))
      (node (ref "U4") (pin "32") (pinfunction "RFIO_LF_32") (pintype "bidirectional"))
    )
    (net (code "103") (name "Net-(U4-SCK)") (class "Default")
      (node (ref "R16") (pin "2") (pinfunction "2_2") (pintype "passive"))
      (node (ref "U4") (pin "7") (pinfunction "SCK_7") (pintype "bidirectional"))
    )
    (net (code "104") (name "Net-(U4-SCL)") (class "Default")
      (node (ref "R22") (pin "1") (pinfunction "1_1") (pintype "passive"))
      (node (ref "U4") (pin "24") (pinfunction "SCL_24") (pintype "bidirectional"))
    )
    (net (code "105") (name "Net-(U4-SDA)") (class "Default")
      (node (ref "R20") (pin "1") (pinfunction "1_1") (pintype "passive"))
      (node (ref "U4") (pin "25") (pinfunction "SDA_25") (pintype "bidirectional"))
    )
    (net (code "106") (name "Net-(U4-USART_RX)") (class "Default")
      (node (ref "R24") (pin "1") (pinfunction "1_1") (pintype "passive"))
      (node (ref "U4") (pin "23") (pinfunction "USART_RX_23") (pintype "bidirectional"))
    )
    (net (code "107") (name "Net-(U4-USART_TX)") (class "Default")
      (node (ref "R25") (pin "1") (pinfunction "1_1") (pintype "passive"))
      (node (ref "U4") (pin "22") (pinfunction "USART_TX_22") (pintype "bidirectional"))
    )
    (net (code "108") (name "Net-(U10-ISET1)") (class "Default")
      (node (ref "R55") (pin "2") (pinfunction "2_2") (pintype "passive"))
      (node (ref "U10") (pin "11") (pinfunction "ISET1_11") (pintype "bidirectional"))
    )
    (net (code "109") (name "Net-(U10-ISET2)") (class "Default")
      (node (ref "R54") (pin "2") (pinfunction "2_2") (pintype "passive"))
      (node (ref "U10") (pin "12") (pinfunction "ISET2_12") (pintype "bidirectional"))
    )
    (net (code "110") (name "Net-(U10-NTC)") (class "Default")
      (node (ref "R48") (pin "1") (pinfunction "1_1") (pintype "passive"))
      (node (ref "R53") (pin "2") (pinfunction "2_2") (pintype "passive"))
      (node (ref "U10") (pin "7") (pinfunction "NTC_7") (pintype "bidirectional"))
    )
    (net (code "111") (name "Net-(U10-PGND)") (class "Default")
      (node (ref "R47") (pin "1") (pinfunction "1_1") (pintype "passive"))
      (node (ref "U10") (pin "5") (pinfunction "PGND_5") (pintype "bidirectional"))
    )
    (net (code "112") (name "PA30_SWCLK") (class "Default")
      (node (ref "J2") (pin "3") (pinfunction "3_3") (pintype "bidirectional"))
      (node (ref "R12") (pin "1") (pinfunction "1_1") (pintype "passive"))
      (node (ref "U5") (pin "45") (pinfunction "PA30/EIC/SCOM1PAD2/TC1_45") (pintype "bidirectional"))
    )
    (net (code "113") (name "PA31_SWDIO") (class "Default")
      (node (ref "J2") (pin "4") (pinfunction "4_4") (pintype "bidirectional"))
      (node (ref "R11") (pin "1") (pinfunction "1_1") (pintype "passive"))
      (node (ref "U5") (pin "46") (pinfunction "PA31/EIC/SCOM1PAD3/TC1_46") (pintype "bidirectional"))
    )
    (net (code "114") (name "RF_IN") (class "Default")
      (node (ref "U1") (pin "6") (pinfunction "RFOUT_6") (pintype "bidirectional"))
      (node (ref "U2") (pin "11") (pinfunction "RF_IN_11") (pintype "bidirectional"))
    )
    (net (code "115") (name "TARGET_USB-N") (class "Default")
      (node (ref "R42") (pin "2") (pinfunction "2_2") (pintype "passive"))
      (node (ref "U5") (pin "33") (pinfunction "PA24/EIC/SCOM3PAD2+/TC5_33") (pintype "bidirectional"))
    )
    (net (code "116") (name "TARGET_USB-P") (class "Default")
      (node (ref "R43") (pin "2") (pinfunction "2_2") (pintype "passive"))
      (node (ref "U5") (pin "34") (pinfunction "PA25/EIC/SCOM3PAD3+/TC5_34") (pintype "bidirectional"))
    )
    (net (code "117") (name "U5V") (class "Default")
      (node (ref "C35") (pin "2") (pinfunction "2_2") (pintype "passive"))
      (node (ref "C36") (pin "2") (pinfunction "2_2") (pintype "passive"))
      (node (ref "C37") (pin "2") (pinfunction "2_2") (pintype "passive"))
      (node (ref "F1") (pin "2") (pinfunction "2_2") (pintype "passive"))
      (node (ref "F2") (pin "2") (pinfunction "2_2") (pintype "passive"))
      (node (ref "R46") (pin "1") (pinfunction "1_1") (pintype "passive"))
      (node (ref "R48") (pin "2") (pinfunction "2_2") (pintype "passive"))
      (node (ref "U10") (pin "2") (pinfunction "IN_2") (pintype "bidirectional"))
      (node (ref "U9") (pin "28") (pinfunction "5V_28") (pintype "bidirectional"))
    )
    (net (code "118") (name "USB_ID") (class "Default")
      (node (ref "J4") (pin "4") (pinfunction "ID_4") (pintype "bidirectional"))
    )
    (net (code "119") (name "VCC_RF") (class "Default")
      (node (ref "R1") (pin "2") (pinfunction "2_2") (pintype "passive"))
      (node (ref "U2") (pin "14") (pinfunction "VCC_RF_14") (pintype "power_in"))
    )
    (net (code "120") (name "VIN") (class "Default")
      (node (ref "C26") (pin "2") (pinfunction "2_2") (pintype "passive"))
      (node (ref "C29") (pin "2") (pinfunction "2_2") (pintype "passive"))
      (node (ref "C38") (pin "2") (pinfunction "2_2") (pintype "passive"))
      (node (ref "C39") (pin "+") (pinfunction "+_+") (pintype "passive"))
      (node (ref "CHG") (pin "+") (pinfunction "+_+") (pintype "passive"))
      (node (ref "J3") (pin "1") (pinfunction "1_1") (pintype "bidirectional"))
      (node (ref "L3") (pin "2") (pinfunction "2_2") (pintype "passive"))
      (node (ref "Q2") (pin "2") (pinfunction "S_2") (pintype "passive"))
      (node (ref "R40") (pin "1") (pinfunction "1_1") (pintype "passive"))
      (node (ref "R46") (pin "2") (pinfunction "2_2") (pintype "passive"))
      (node (ref "R49") (pin "2") (pinfunction "2_2") (pintype "passive"))
      (node (ref "U10") (pin "1") (pinfunction "SYS_1") (pintype "bidirectional"))
      (node (ref "U10") (pin "15") (pinfunction "SYS_15") (pintype "bidirectional"))
      (node (ref "U6") (pin "3") (pinfunction "VIN_3") (pintype "input"))
      (node (ref "U7") (pin "3") (pinfunction "VIN_3") (pintype "input"))
    )
    (net (code "121") (name "unconnected-(DEBUG-ID-Pad4)") (class "Default")
      (node (ref "DEBUG") (pin "4") (pinfunction "ID_4") (pintype "bidirectional"))
    )
    (net (code "122") (name "unconnected-(U2-NC-Pad7)") (class "Default")
      (node (ref "U2") (pin "7") (pinfunction "NC_7") (pintype "bidirectional"))
    )
    (net (code "123") (name "unconnected-(U2-NC-Pad15)") (class "Default")
      (node (ref "U2") (pin "15") (pinfunction "NC_15") (pintype "bidirectional"))
    )
    (net (code "124") (name "unconnected-(U2-RESET-Pad9)") (class "Default")
      (node (ref "U2") (pin "9") (pinfunction "RESET_9") (pintype "bidirectional"))
    )
    (net (code "125") (name "unconnected-(U2-TIMER-Pad18)") (class "Default")
      (node (ref "U2") (pin "18") (pinfunction "TIMER_18") (pintype "bidirectional"))
    )
    (net (code "126") (name "unconnected-(U4-NC-Pad17)") (class "Default")
      (node (ref "U4") (pin "17") (pinfunction "NC_17") (pintype "bidirectional"))
    )
    (net (code "127") (name "unconnected-(U4-NC-Pad18)") (class "Default")
      (node (ref "U4") (pin "18") (pinfunction "NC_18") (pintype "bidirectional"))
    )
    (net (code "128") (name "unconnected-(U4-NC-Pad19)") (class "Default")
      (node (ref "U4") (pin "19") (pinfunction "NC_19") (pintype "bidirectional"))
    )
    (net (code "129") (name "unconnected-(U4-PA3-Pad20)") (class "Default")
      (node (ref "U4") (pin "20") (pinfunction "PA3_20") (pintype "bidirectional"))
    )
    (net (code "130") (name "unconnected-(U4-PA8-Pad3)") (class "Default")
      (node (ref "U4") (pin "3") (pinfunction "PA8_3") (pintype "bidirectional"))
    )
    (net (code "131") (name "unconnected-(U4-PB3-Pad15)") (class "Default")
      (node (ref "U4") (pin "15") (pinfunction "PB3_15") (pintype "bidirectional"))
    )
    (net (code "132") (name "unconnected-(U9-RESERVED-Pad32)") (class "Default")
      (node (ref "U9") (pin "32") (pinfunction "RESERVED_32") (pintype "bidirectional"))
    )
    (net (code "133") (name "unconnected-(U9-VIN-Pad25)") (class "Default")
      (node (ref "U9") (pin "25") (pinfunction "VIN_25") (pintype "bidirectional"))
    )
  )
)
